# rpusb.net
KiCad netlist of a schematic drawn in EAGLE
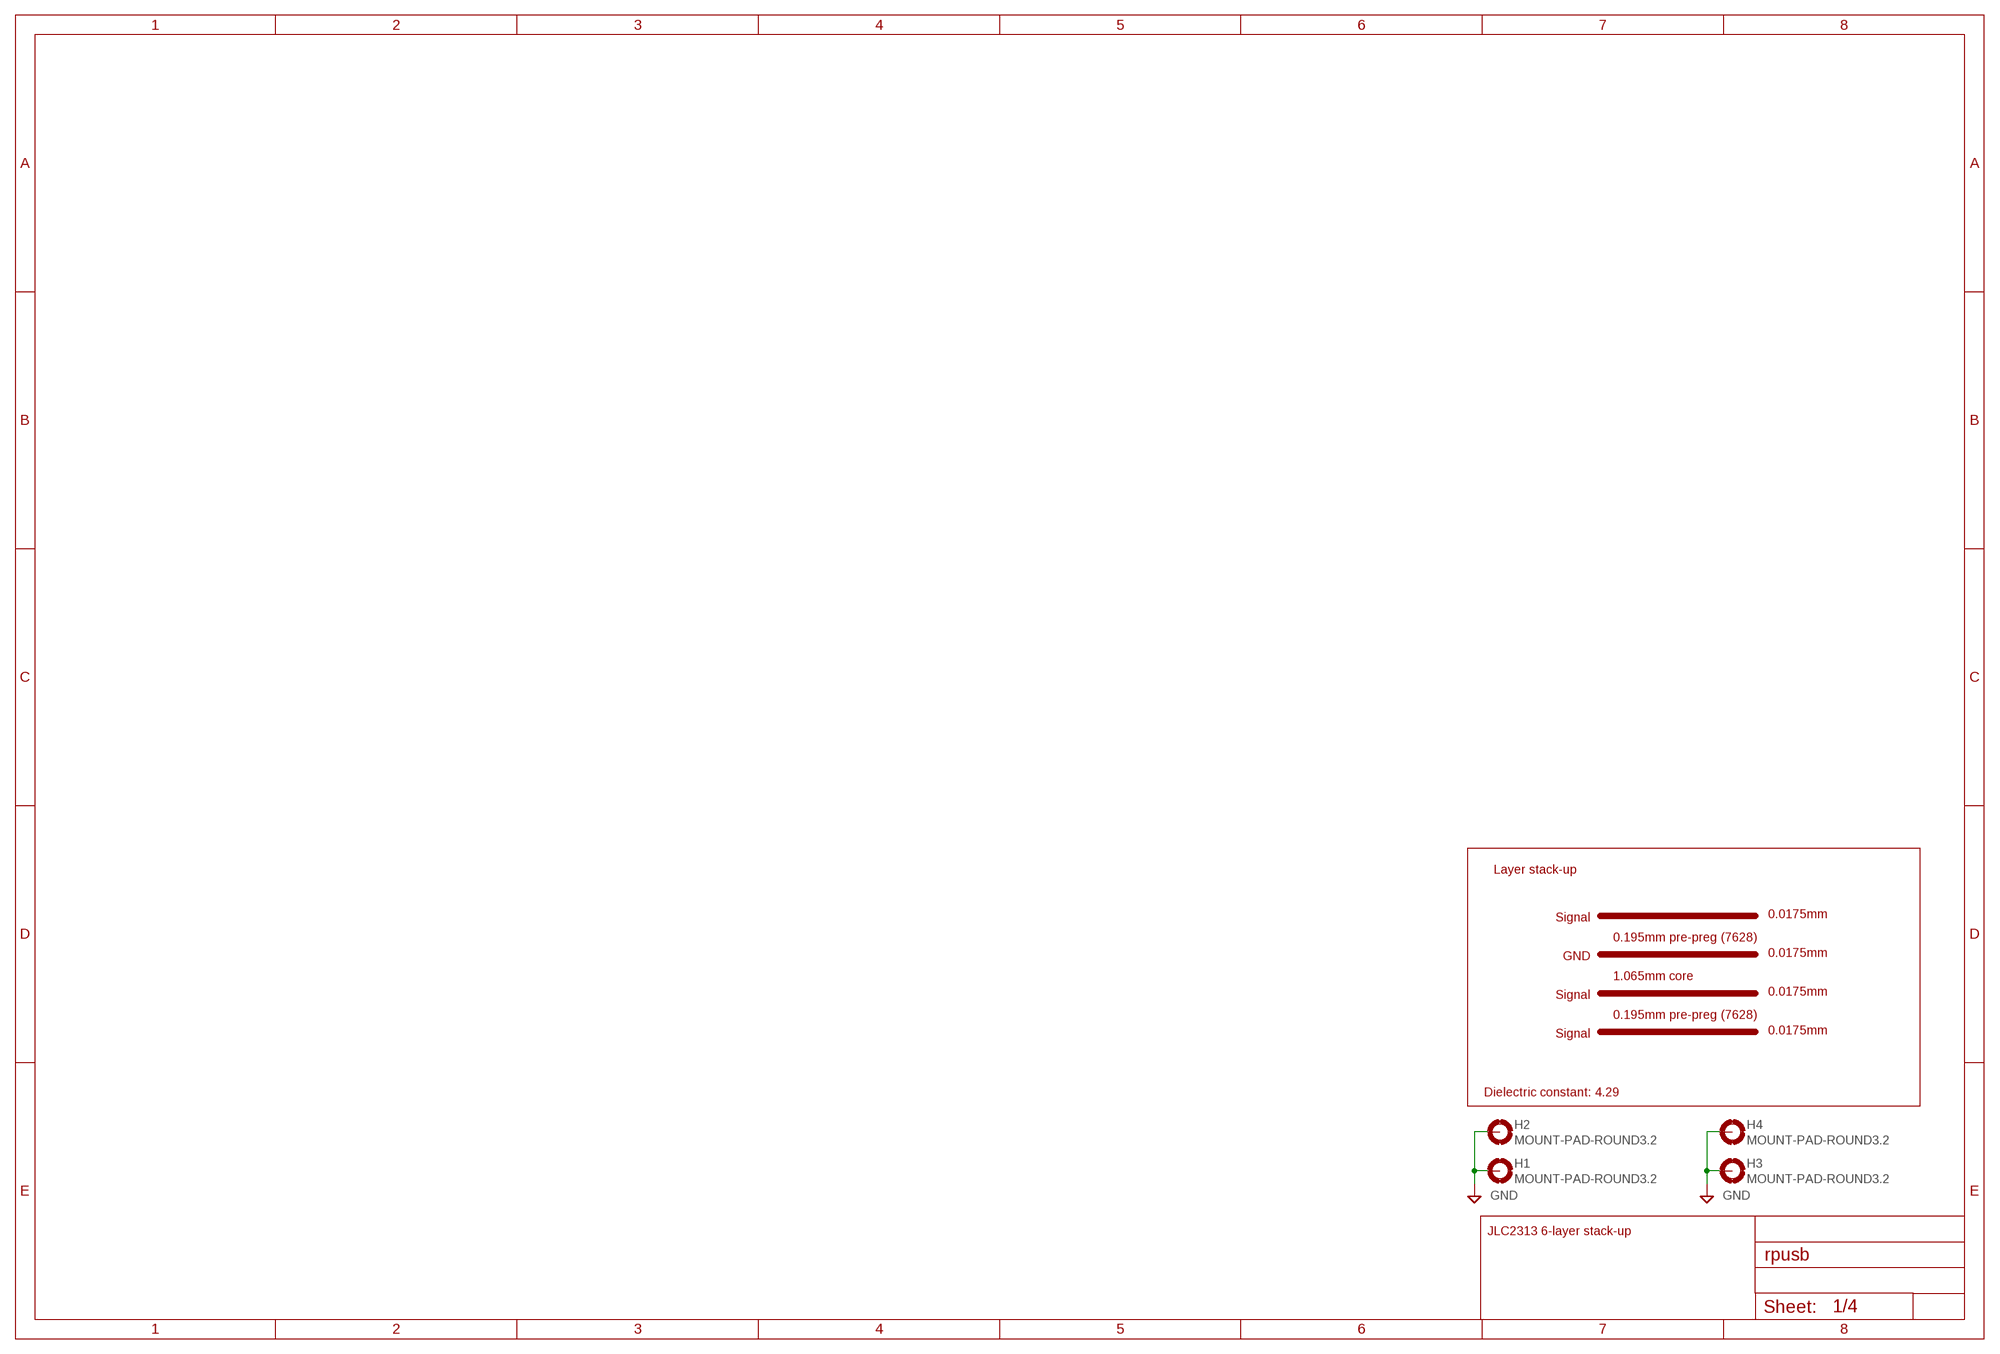
[diagram p0: schematic, sheet 1]
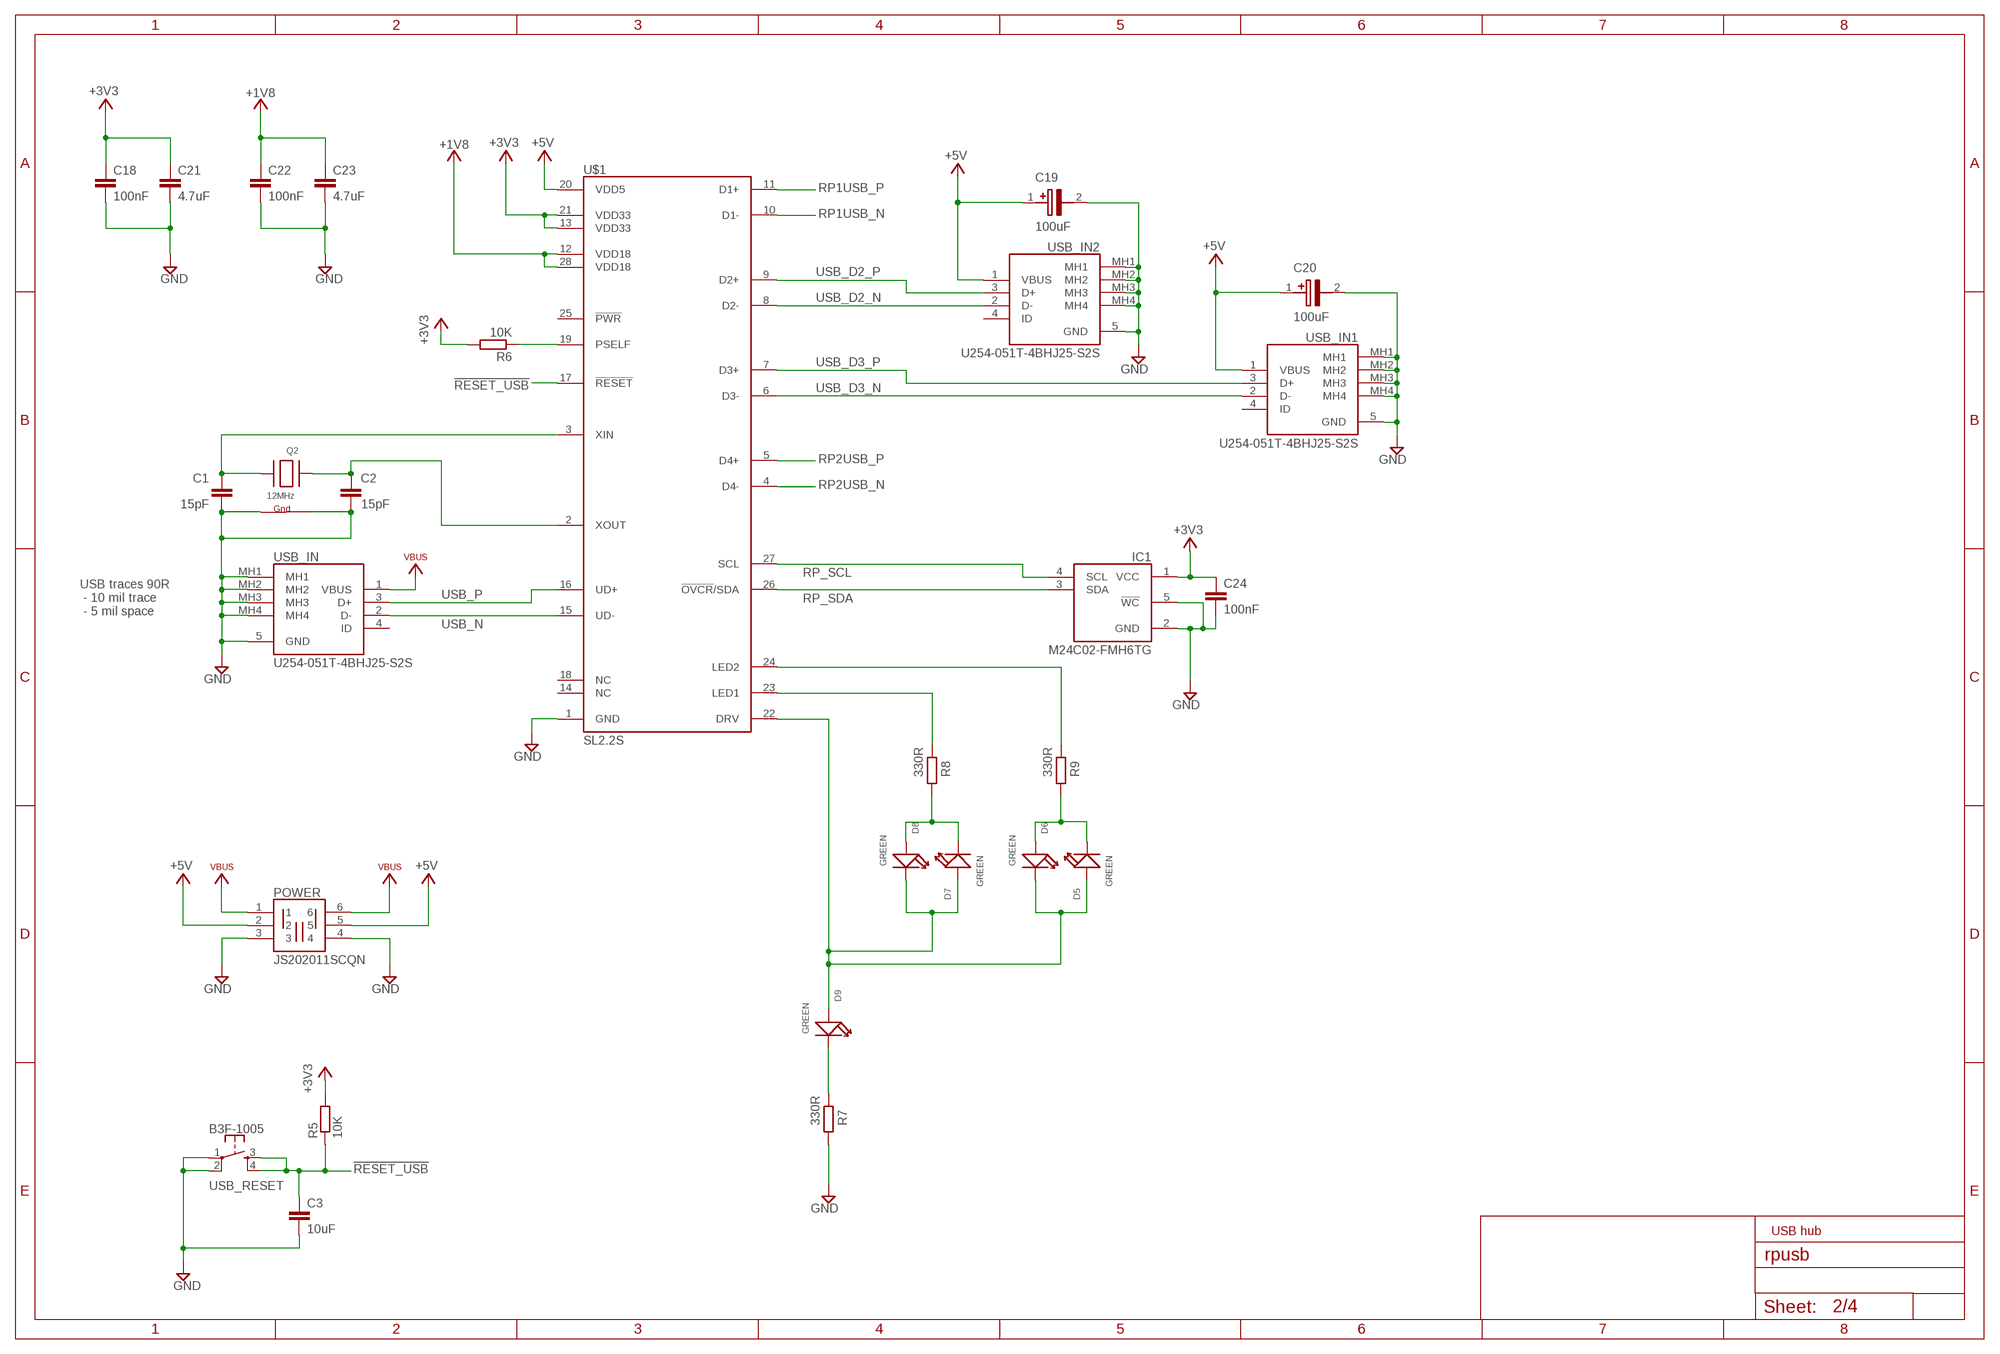
[diagram p1: schematic, sheet 2]
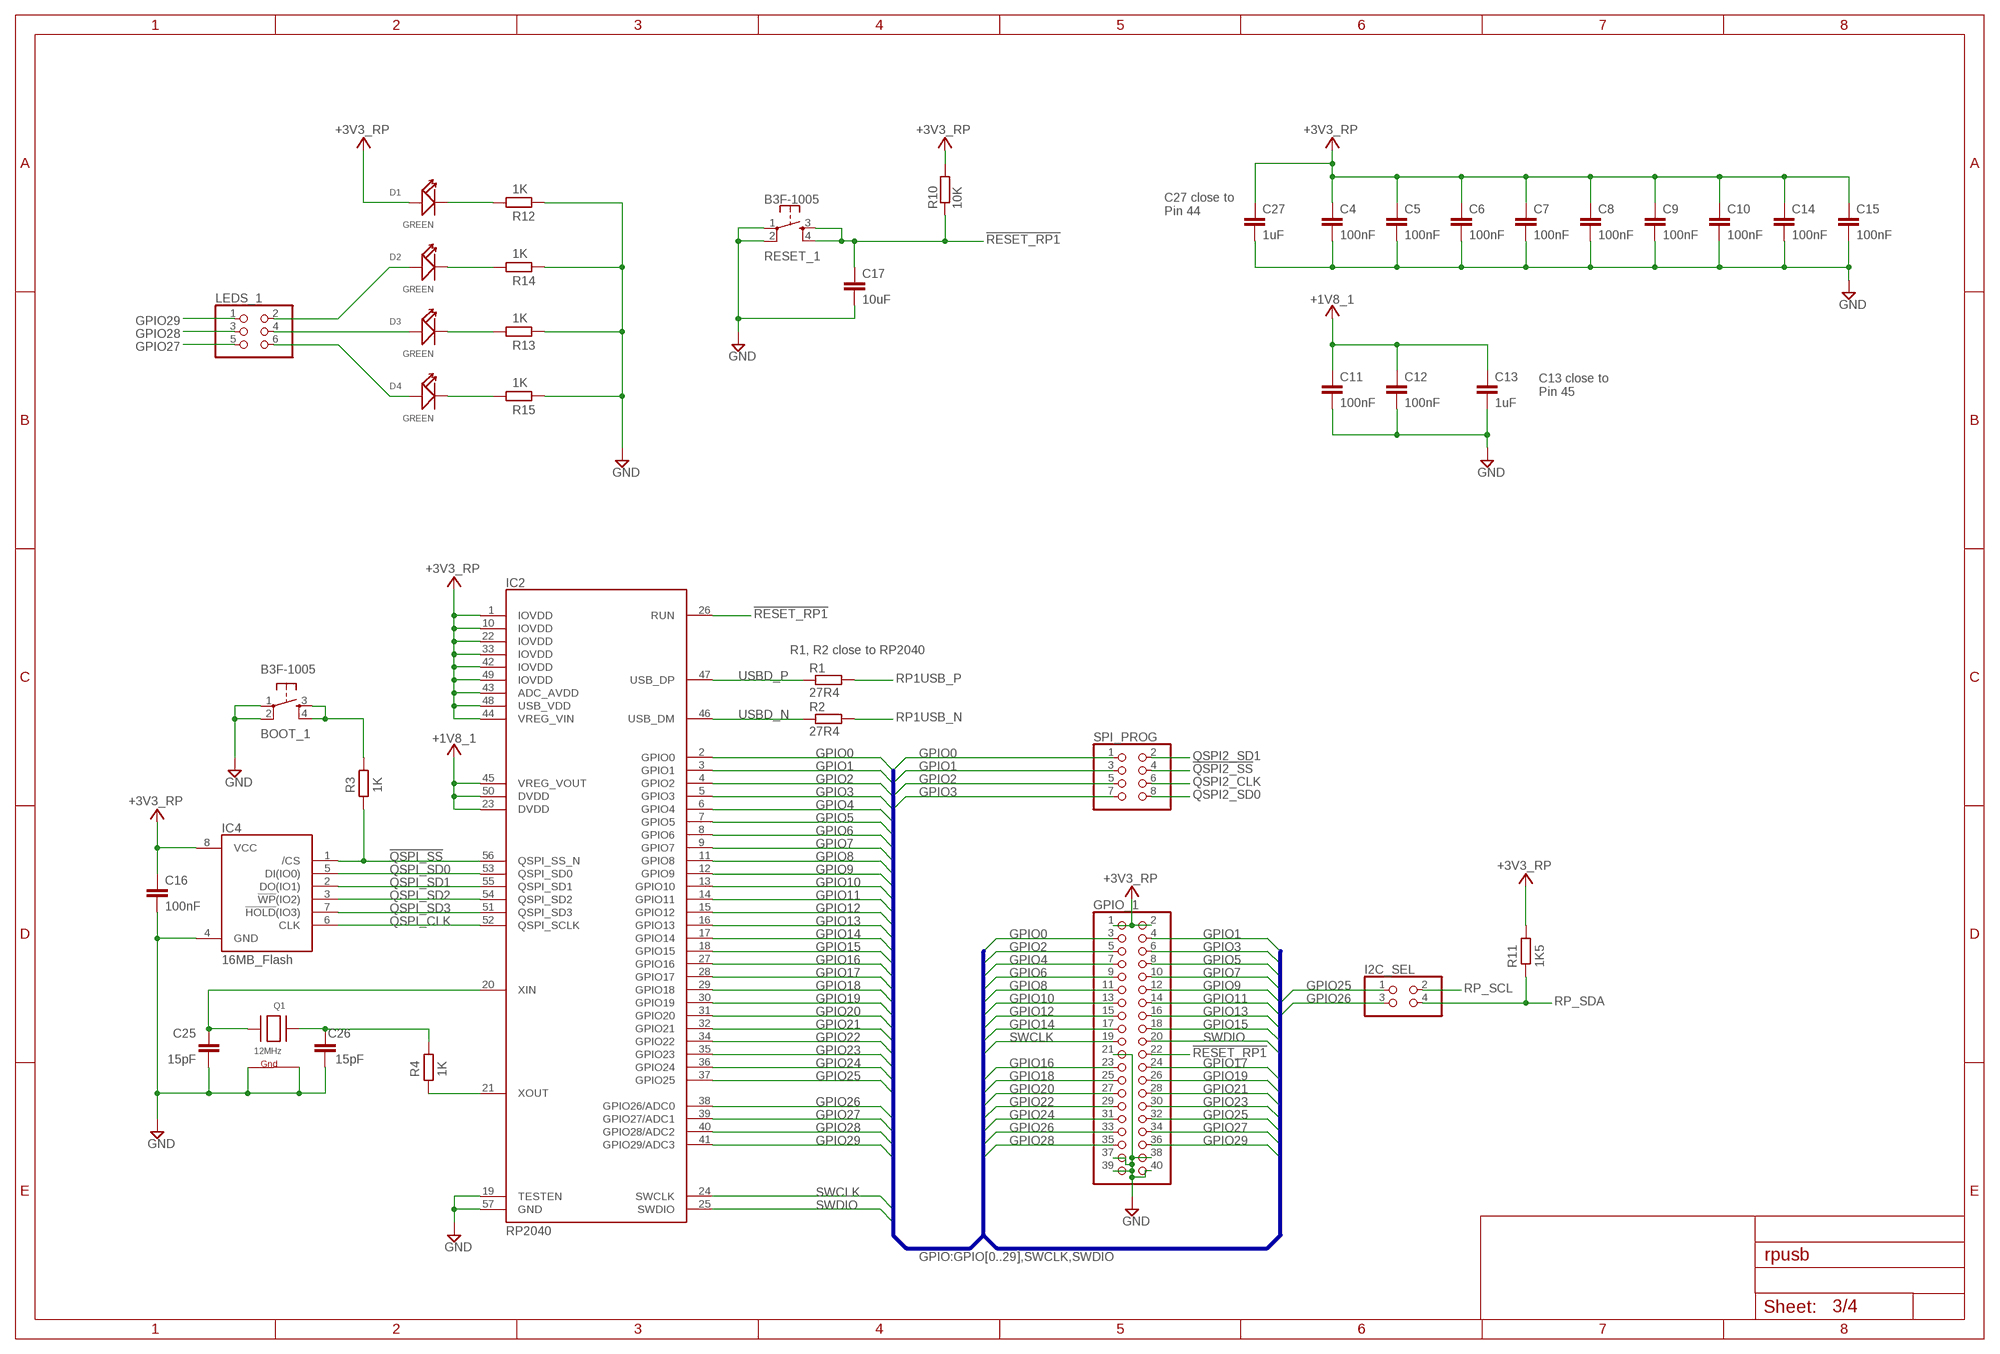
[diagram p2: schematic, sheet 3]
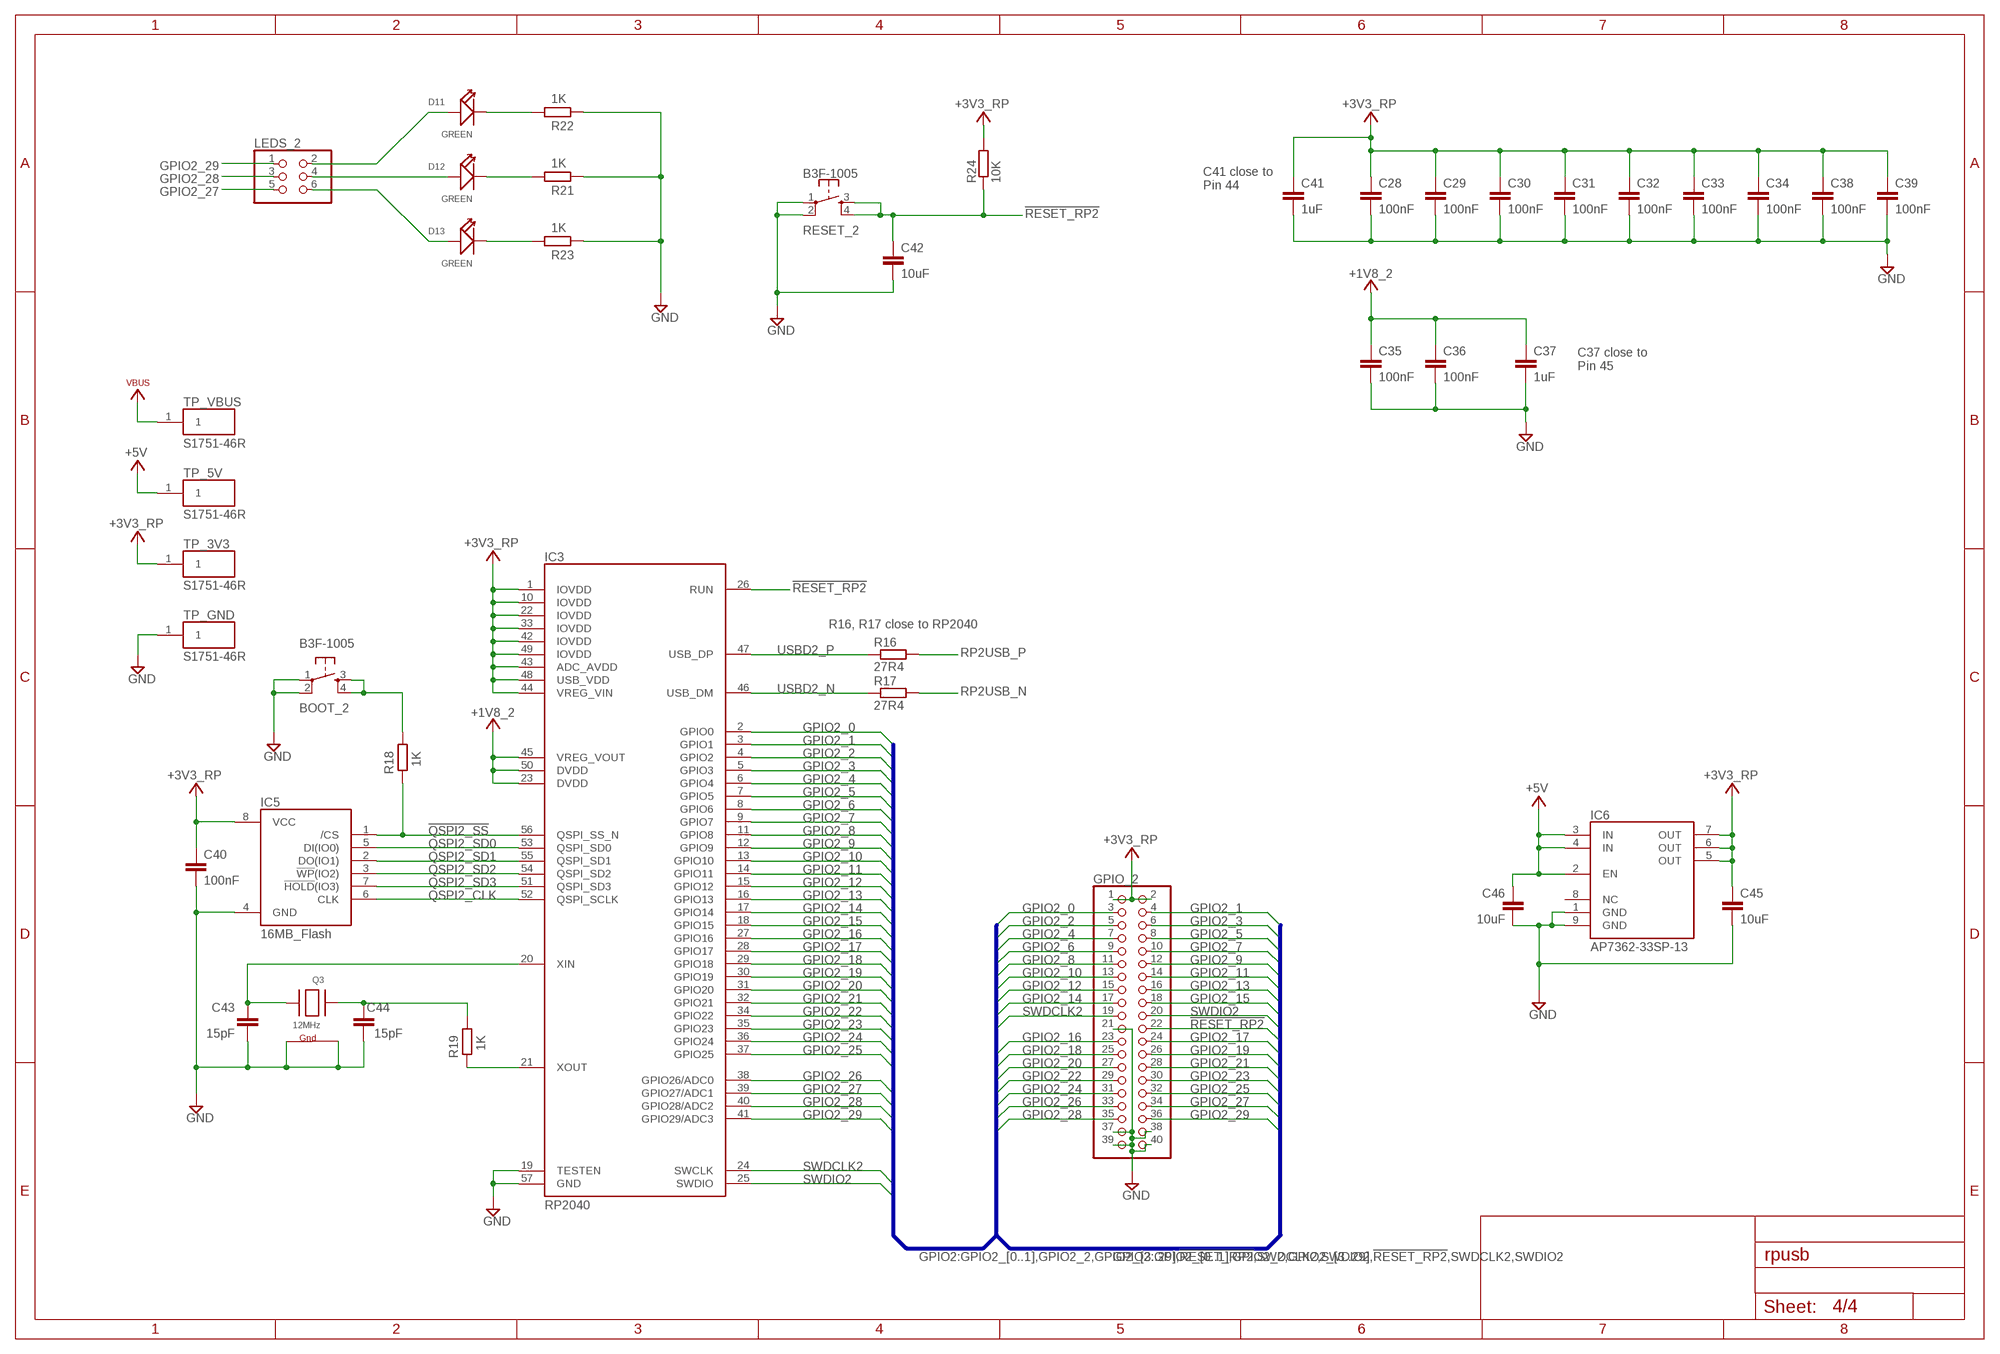
[diagram p3: schematic, sheet 4]

(export (version "E")
  (design (tool "Eeschema 10.0.6"))
  (components
    (comp (ref "C1")
      (value "15pF")
      (footprint "eagle-import:C0201")
      (libsource (lib "eagle-import") (part "C-EUC0201"))
    )
    (comp (ref "C2")
      (value "15pF")
      (footprint "eagle-import:C0201")
      (libsource (lib "eagle-import") (part "C-EUC0201"))
    )
    (comp (ref "C3")
      (value "10uF")
      (footprint "eagle-import:C0402")
      (fields (field (name "USE") "CL05A106MP5NUNC"))
      (libsource (lib "eagle-import") (part "C-EUC0402"))
    )
    (comp (ref "C18")
      (value "100nF")
      (footprint "eagle-import:C0201")
      (libsource (lib "eagle-import") (part "C-EUC0201"))
    )
    (comp (ref "C19")
      (value "100uF")
      (footprint "eagle-import:CAPAE530X550N")
      (fields
        (field (name "MANUFACTURER_PART_NUMBER") "865080142007")
        (field (name "MOUSER_PART_NUMBER") "710-865080142007")
      )
      (libsource (lib "eagle-import") (part "865080142007"))
    )
    (comp (ref "C20")
      (value "100uF")
      (footprint "eagle-import:CAPAE530X550N")
      (fields
        (field (name "MANUFACTURER_PART_NUMBER") "865080142007")
        (field (name "MOUSER_PART_NUMBER") "710-865080142007")
      )
      (libsource (lib "eagle-import") (part "865080142007"))
    )
    (comp (ref "C21")
      (value "4.7uF")
      (footprint "eagle-import:C0402")
      (libsource (lib "eagle-import") (part "C-EUC0402"))
    )
    (comp (ref "C22")
      (value "100nF")
      (footprint "eagle-import:C0201")
      (libsource (lib "eagle-import") (part "C-EUC0201"))
    )
    (comp (ref "C23")
      (value "4.7uF")
      (footprint "eagle-import:C0402")
      (libsource (lib "eagle-import") (part "C-EUC0402"))
    )
    (comp (ref "C24")
      (value "100nF")
      (footprint "eagle-import:C0201")
      (libsource (lib "eagle-import") (part "C-EUC0201"))
    )
    (comp (ref "D5")
      (value "GREEN")
      (footprint "eagle-import:LED-0603")
      (fields (field (name "MPN") "19-217-BHC-ZL1M2RY-3T"))
      (libsource (lib "eagle-import") (part "SMD-LED-CLEAR-BLUE(0603)"))
    )
    (comp (ref "D6")
      (value "GREEN")
      (footprint "eagle-import:LED-0603")
      (fields (field (name "MPN") "19-217-BHC-ZL1M2RY-3T"))
      (libsource (lib "eagle-import") (part "SMD-LED-CLEAR-BLUE(0603)"))
    )
    (comp (ref "D7")
      (value "GREEN")
      (footprint "eagle-import:LED-0603")
      (fields (field (name "MPN") "19-217-BHC-ZL1M2RY-3T"))
      (libsource (lib "eagle-import") (part "SMD-LED-CLEAR-BLUE(0603)"))
    )
    (comp (ref "D8")
      (value "GREEN")
      (footprint "eagle-import:LED-0603")
      (fields (field (name "MPN") "19-217-BHC-ZL1M2RY-3T"))
      (libsource (lib "eagle-import") (part "SMD-LED-CLEAR-BLUE(0603)"))
    )
    (comp (ref "D9")
      (value "GREEN")
      (footprint "eagle-import:LED-0603")
      (fields (field (name "MPN") "19-217-BHC-ZL1M2RY-3T"))
      (libsource (lib "eagle-import") (part "SMD-LED-CLEAR-BLUE(0603)"))
    )
    (comp (ref "IC1")
      (value "M24C02-FMH6TG")
      (footprint "eagle-import:M24C32FMH6TG")
      (fields (field (name "MOUSER_PART_NUMBER") "511-M24C02-FMH6TG"))
      (libsource (lib "eagle-import") (part "M24C02-FMH6TG"))
    )
    (comp (ref "POWER")
      (value "JS202011SCQN")
      (footprint "eagle-import:JS202011SCQN")
      (fields (field (name "MOUSER_PART_NUMBER") "611-JS202011SCQN"))
      (libsource (lib "eagle-import") (part "JS202011SCQN"))
    )
    (comp (ref "Q2")
      (value "12MHz")
      (footprint "eagle-import:NX3225")
      (libsource (lib "eagle-import") (part "XTAL-4-3225"))
    )
    (comp (ref "R5")
      (value "10K")
      (footprint "eagle-import:R0201")
      (fields (field (name "USE") "CR0201-JW-103GLF"))
      (libsource (lib "eagle-import") (part "R-EU_R0201"))
    )
    (comp (ref "R6")
      (value "10K")
      (footprint "eagle-import:R0201")
      (fields (field (name "USE") "CR0201-JW-103GLF"))
      (libsource (lib "eagle-import") (part "R-EU_R0201"))
    )
    (comp (ref "R7")
      (value "330R")
      (footprint "eagle-import:R0201")
      (libsource (lib "eagle-import") (part "R-EU_R0201"))
    )
    (comp (ref "R8")
      (value "330R")
      (footprint "eagle-import:R0201")
      (libsource (lib "eagle-import") (part "R-EU_R0201"))
    )
    (comp (ref "R9")
      (value "330R")
      (footprint "eagle-import:R0201")
      (libsource (lib "eagle-import") (part "R-EU_R0201"))
    )
    (comp (ref "U$1")
      (value "SL2.2S")
      (footprint "eagle-import:SSOP28-0.635")
      (libsource (lib "eagle-import") (part "SL2.2S"))
    )
    (comp (ref "USB_IN")
      (value "U254-051T-4BHJ25-S2S")
      (footprint "eagle-import:U254051T4BHJ25S2S")
      (libsource (lib "eagle-import") (part "U254-051T-4BHJ25-S2S"))
    )
    (comp (ref "USB_IN1")
      (value "U254-051T-4BHJ25-S2S")
      (footprint "eagle-import:U254051T4BHJ25S2S")
      (libsource (lib "eagle-import") (part "U254-051T-4BHJ25-S2S"))
    )
    (comp (ref "USB_IN2")
      (value "U254-051T-4BHJ25-S2S")
      (footprint "eagle-import:U254051T4BHJ25S2S")
      (libsource (lib "eagle-import") (part "U254-051T-4BHJ25-S2S"))
    )
    (comp (ref "USB_RESET")
      (value "B3F-1005")
      (footprint "eagle-import:TACTILE-PTH")
      (fields (field (name "USE") "B3F-1005"))
      (libsource (lib "eagle-import") (part "TAC_SWITCHPTH"))
    )
    (comp (ref "BOOT_1")
      (value "B3F-1005")
      (footprint "eagle-import:TACTILE-PTH")
      (fields (field (name "USE") "B3F-1005"))
      (libsource (lib "eagle-import") (part "TAC_SWITCHPTH"))
    )
    (comp (ref "C4")
      (value "100nF")
      (footprint "eagle-import:C0201")
      (libsource (lib "eagle-import") (part "C-EUC0201"))
    )
    (comp (ref "C5")
      (value "100nF")
      (footprint "eagle-import:C0201")
      (libsource (lib "eagle-import") (part "C-EUC0201"))
    )
    (comp (ref "C6")
      (value "100nF")
      (footprint "eagle-import:C0201")
      (libsource (lib "eagle-import") (part "C-EUC0201"))
    )
    (comp (ref "C7")
      (value "100nF")
      (footprint "eagle-import:C0201")
      (libsource (lib "eagle-import") (part "C-EUC0201"))
    )
    (comp (ref "C8")
      (value "100nF")
      (footprint "eagle-import:C0201")
      (libsource (lib "eagle-import") (part "C-EUC0201"))
    )
    (comp (ref "C9")
      (value "100nF")
      (footprint "eagle-import:C0201")
      (libsource (lib "eagle-import") (part "C-EUC0201"))
    )
    (comp (ref "C10")
      (value "100nF")
      (footprint "eagle-import:C0201")
      (libsource (lib "eagle-import") (part "C-EUC0201"))
    )
    (comp (ref "C11")
      (value "100nF")
      (footprint "eagle-import:C0201")
      (libsource (lib "eagle-import") (part "C-EUC0201"))
    )
    (comp (ref "C12")
      (value "100nF")
      (footprint "eagle-import:C0201")
      (libsource (lib "eagle-import") (part "C-EUC0201"))
    )
    (comp (ref "C13")
      (value "1uF")
      (footprint "eagle-import:C0201")
      (libsource (lib "eagle-import") (part "C-EUC0201"))
    )
    (comp (ref "C14")
      (value "100nF")
      (footprint "eagle-import:C0201")
      (libsource (lib "eagle-import") (part "C-EUC0201"))
    )
    (comp (ref "C15")
      (value "100nF")
      (footprint "eagle-import:C0201")
      (libsource (lib "eagle-import") (part "C-EUC0201"))
    )
    (comp (ref "C16")
      (value "100nF")
      (footprint "eagle-import:C0201")
      (libsource (lib "eagle-import") (part "C-EUC0201"))
    )
    (comp (ref "C17")
      (value "10uF")
      (footprint "eagle-import:C0402")
      (fields (field (name "USE") "CL05A106MP5NUNC"))
      (libsource (lib "eagle-import") (part "C-EUC0402"))
    )
    (comp (ref "C25")
      (value "15pF")
      (footprint "eagle-import:C0201")
      (libsource (lib "eagle-import") (part "C-EUC0201"))
    )
    (comp (ref "C26")
      (value "15pF")
      (footprint "eagle-import:C0201")
      (libsource (lib "eagle-import") (part "C-EUC0201"))
    )
    (comp (ref "C27")
      (value "1uF")
      (footprint "eagle-import:C0201")
      (libsource (lib "eagle-import") (part "C-EUC0201"))
    )
    (comp (ref "D1")
      (value "GREEN")
      (footprint "eagle-import:LED-0603")
      (fields (field (name "MPN") "19-217-BHC-ZL1M2RY-3T"))
      (libsource (lib "eagle-import") (part "SMD-LED-CLEAR-BLUE(0603)"))
    )
    (comp (ref "D2")
      (value "GREEN")
      (footprint "eagle-import:LED-0603")
      (fields (field (name "MPN") "19-217-BHC-ZL1M2RY-3T"))
      (libsource (lib "eagle-import") (part "SMD-LED-CLEAR-BLUE(0603)"))
    )
    (comp (ref "D3")
      (value "GREEN")
      (footprint "eagle-import:LED-0603")
      (fields (field (name "MPN") "19-217-BHC-ZL1M2RY-3T"))
      (libsource (lib "eagle-import") (part "SMD-LED-CLEAR-BLUE(0603)"))
    )
    (comp (ref "D4")
      (value "GREEN")
      (footprint "eagle-import:LED-0603")
      (fields (field (name "MPN") "19-217-BHC-ZL1M2RY-3T"))
      (libsource (lib "eagle-import") (part "SMD-LED-CLEAR-BLUE(0603)"))
    )
    (comp (ref "GPIO_1")
      (value "PINHD-2X20")
      (footprint "eagle-import:2X20")
      (libsource (lib "eagle-import") (part "PINHD-2X20"))
    )
    (comp (ref "I2C_SEL")
      (value "PINHD-2X2")
      (footprint "eagle-import:2X02")
      (libsource (lib "eagle-import") (part "PINHD-2X2"))
    )
    (comp (ref "IC2")
      (value "RP2040")
      (footprint "eagle-import:QFN40P700X700X90-57N")
      (libsource (lib "eagle-import") (part "RP2040"))
    )
    (comp (ref "IC4")
      (value "16MB_Flash")
      (footprint "eagle-import:SOIC127P790X216-8N")
      (fields
        (field (name "ARROW_PART_NUMBER") "W25Q128JVSIM TR")
        (field (name "MOUSER_PART_NUMBER") "454-W25Q128JVSIMTR")
      )
      (libsource (lib "eagle-import") (part "W25Q128JVSIM_TR"))
    )
    (comp (ref "LEDS_1")
      (value "PINHD-2X3")
      (footprint "eagle-import:2X03")
      (libsource (lib "eagle-import") (part "PINHD-2X3"))
    )
    (comp (ref "Q1")
      (value "12MHz")
      (footprint "eagle-import:NX3225")
      (libsource (lib "eagle-import") (part "XTAL-4-3225"))
    )
    (comp (ref "R1")
      (value "27R4")
      (footprint "eagle-import:R0201")
      (libsource (lib "eagle-import") (part "R-EU_R0201"))
    )
    (comp (ref "R2")
      (value "27R4")
      (footprint "eagle-import:R0201")
      (libsource (lib "eagle-import") (part "R-EU_R0201"))
    )
    (comp (ref "R3")
      (value "1K")
      (footprint "eagle-import:R0201")
      (libsource (lib "eagle-import") (part "R-EU_R0201"))
    )
    (comp (ref "R4")
      (value "1K")
      (footprint "eagle-import:R0201")
      (libsource (lib "eagle-import") (part "R-EU_R0201"))
    )
    (comp (ref "R10")
      (value "10K")
      (footprint "eagle-import:R0201")
      (fields (field (name "USE") "CR0201-JW-103GLF"))
      (libsource (lib "eagle-import") (part "R-EU_R0201"))
    )
    (comp (ref "R11")
      (value "1K5")
      (footprint "eagle-import:R0201")
      (libsource (lib "eagle-import") (part "R-EU_R0201"))
    )
    (comp (ref "R12")
      (value "1K")
      (footprint "eagle-import:R0201")
      (libsource (lib "eagle-import") (part "R-EU_R0201"))
    )
    (comp (ref "R13")
      (value "1K")
      (footprint "eagle-import:R0201")
      (libsource (lib "eagle-import") (part "R-EU_R0201"))
    )
    (comp (ref "R14")
      (value "1K")
      (footprint "eagle-import:R0201")
      (libsource (lib "eagle-import") (part "R-EU_R0201"))
    )
    (comp (ref "R15")
      (value "1K")
      (footprint "eagle-import:R0201")
      (libsource (lib "eagle-import") (part "R-EU_R0201"))
    )
    (comp (ref "RESET_1")
      (value "B3F-1005")
      (footprint "eagle-import:TACTILE-PTH")
      (fields (field (name "USE") "B3F-1005"))
      (libsource (lib "eagle-import") (part "TAC_SWITCHPTH"))
    )
    (comp (ref "SPI_PROG")
      (value "PINHD-2X4")
      (footprint "eagle-import:2X04")
      (libsource (lib "eagle-import") (part "PINHD-2X4"))
    )
    (comp (ref "H1")
      (value "MOUNT-PAD-ROUND3.2")
      (footprint "eagle-import:3,2-PAD")
      (libsource (lib "eagle-import") (part "MOUNT-PAD-ROUND3.2"))
    )
    (comp (ref "H2")
      (value "MOUNT-PAD-ROUND3.2")
      (footprint "eagle-import:3,2-PAD")
      (libsource (lib "eagle-import") (part "MOUNT-PAD-ROUND3.2"))
    )
    (comp (ref "H3")
      (value "MOUNT-PAD-ROUND3.2")
      (footprint "eagle-import:3,2-PAD")
      (libsource (lib "eagle-import") (part "MOUNT-PAD-ROUND3.2"))
    )
    (comp (ref "H4")
      (value "MOUNT-PAD-ROUND3.2")
      (footprint "eagle-import:3,2-PAD")
      (libsource (lib "eagle-import") (part "MOUNT-PAD-ROUND3.2"))
    )
    (comp (ref "BOOT_2")
      (value "B3F-1005")
      (footprint "eagle-import:TACTILE-PTH")
      (fields (field (name "USE") "B3F-1005"))
      (libsource (lib "eagle-import") (part "TAC_SWITCHPTH"))
    )
    (comp (ref "C28")
      (value "100nF")
      (footprint "eagle-import:C0201")
      (libsource (lib "eagle-import") (part "C-EUC0201"))
    )
    (comp (ref "C29")
      (value "100nF")
      (footprint "eagle-import:C0201")
      (libsource (lib "eagle-import") (part "C-EUC0201"))
    )
    (comp (ref "C30")
      (value "100nF")
      (footprint "eagle-import:C0201")
      (libsource (lib "eagle-import") (part "C-EUC0201"))
    )
    (comp (ref "C31")
      (value "100nF")
      (footprint "eagle-import:C0201")
      (libsource (lib "eagle-import") (part "C-EUC0201"))
    )
    (comp (ref "C32")
      (value "100nF")
      (footprint "eagle-import:C0201")
      (libsource (lib "eagle-import") (part "C-EUC0201"))
    )
    (comp (ref "C33")
      (value "100nF")
      (footprint "eagle-import:C0201")
      (libsource (lib "eagle-import") (part "C-EUC0201"))
    )
    (comp (ref "C34")
      (value "100nF")
      (footprint "eagle-import:C0201")
      (libsource (lib "eagle-import") (part "C-EUC0201"))
    )
    (comp (ref "C35")
      (value "100nF")
      (footprint "eagle-import:C0201")
      (libsource (lib "eagle-import") (part "C-EUC0201"))
    )
    (comp (ref "C36")
      (value "100nF")
      (footprint "eagle-import:C0201")
      (libsource (lib "eagle-import") (part "C-EUC0201"))
    )
    (comp (ref "C37")
      (value "1uF")
      (footprint "eagle-import:C0201")
      (libsource (lib "eagle-import") (part "C-EUC0201"))
    )
    (comp (ref "C38")
      (value "100nF")
      (footprint "eagle-import:C0201")
      (libsource (lib "eagle-import") (part "C-EUC0201"))
    )
    (comp (ref "C39")
      (value "100nF")
      (footprint "eagle-import:C0201")
      (libsource (lib "eagle-import") (part "C-EUC0201"))
    )
    (comp (ref "C40")
      (value "100nF")
      (footprint "eagle-import:C0201")
      (libsource (lib "eagle-import") (part "C-EUC0201"))
    )
    (comp (ref "C41")
      (value "1uF")
      (footprint "eagle-import:C0201")
      (libsource (lib "eagle-import") (part "C-EUC0201"))
    )
    (comp (ref "C42")
      (value "10uF")
      (footprint "eagle-import:C0402")
      (fields (field (name "USE") "CL05A106MP5NUNC"))
      (libsource (lib "eagle-import") (part "C-EUC0402"))
    )
    (comp (ref "C43")
      (value "15pF")
      (footprint "eagle-import:C0201")
      (libsource (lib "eagle-import") (part "C-EUC0201"))
    )
    (comp (ref "C44")
      (value "15pF")
      (footprint "eagle-import:C0201")
      (libsource (lib "eagle-import") (part "C-EUC0201"))
    )
    (comp (ref "C45")
      (value "10uF")
      (footprint "eagle-import:C0402")
      (fields (field (name "USE") "CL05A106MP5NUNC"))
      (libsource (lib "eagle-import") (part "C-EUC0402"))
    )
    (comp (ref "C46")
      (value "10uF")
      (footprint "eagle-import:C0402")
      (fields (field (name "USE") "CL05A106MP5NUNC"))
      (libsource (lib "eagle-import") (part "C-EUC0402"))
    )
    (comp (ref "D11")
      (value "GREEN")
      (footprint "eagle-import:LED-0603")
      (fields (field (name "MPN") "19-217-BHC-ZL1M2RY-3T"))
      (libsource (lib "eagle-import") (part "SMD-LED-CLEAR-BLUE(0603)"))
    )
    (comp (ref "D12")
      (value "GREEN")
      (footprint "eagle-import:LED-0603")
      (fields (field (name "MPN") "19-217-BHC-ZL1M2RY-3T"))
      (libsource (lib "eagle-import") (part "SMD-LED-CLEAR-BLUE(0603)"))
    )
    (comp (ref "D13")
      (value "GREEN")
      (footprint "eagle-import:LED-0603")
      (fields (field (name "MPN") "19-217-BHC-ZL1M2RY-3T"))
      (libsource (lib "eagle-import") (part "SMD-LED-CLEAR-BLUE(0603)"))
    )
    (comp (ref "GPIO_2")
      (value "PINHD-2X20")
      (footprint "eagle-import:2X20")
      (libsource (lib "eagle-import") (part "PINHD-2X20"))
    )
    (comp (ref "IC3")
      (value "RP2040")
      (footprint "eagle-import:QFN40P700X700X90-57N")
      (libsource (lib "eagle-import") (part "RP2040"))
    )
    (comp (ref "IC5")
      (value "16MB_Flash")
      (footprint "eagle-import:SOIC127P790X216-8N")
      (fields
        (field (name "ARROW_PART_NUMBER") "W25Q128JVSIM TR")
        (field (name "MOUSER_PART_NUMBER") "454-W25Q128JVSIMTR")
      )
      (libsource (lib "eagle-import") (part "W25Q128JVSIM_TR"))
    )
    (comp (ref "IC6")
      (value "AP7362-33SP-13")
      (footprint "eagle-import:SOIC127P600X163-9N")
      (fields (field (name "MOUSER_PART_NUMBER") "621-AP7362-33SP-13"))
      (libsource (lib "eagle-import") (part "AP7362-33SP-13"))
    )
    (comp (ref "LEDS_2")
      (value "PINHD-2X3")
      (footprint "eagle-import:2X03")
      (libsource (lib "eagle-import") (part "PINHD-2X3"))
    )
    (comp (ref "Q3")
      (value "12MHz")
      (footprint "eagle-import:NX3225")
      (libsource (lib "eagle-import") (part "XTAL-4-3225"))
    )
    (comp (ref "R16")
      (value "27R4")
      (footprint "eagle-import:R0201")
      (libsource (lib "eagle-import") (part "R-EU_R0201"))
    )
    (comp (ref "R17")
      (value "27R4")
      (footprint "eagle-import:R0201")
      (libsource (lib "eagle-import") (part "R-EU_R0201"))
    )
    (comp (ref "R18")
      (value "1K")
      (footprint "eagle-import:R0201")
      (libsource (lib "eagle-import") (part "R-EU_R0201"))
    )
    (comp (ref "R19")
      (value "1K")
      (footprint "eagle-import:R0201")
      (libsource (lib "eagle-import") (part "R-EU_R0201"))
    )
    (comp (ref "R21")
      (value "1K")
      (footprint "eagle-import:R0201")
      (libsource (lib "eagle-import") (part "R-EU_R0201"))
    )
    (comp (ref "R22")
      (value "1K")
      (footprint "eagle-import:R0201")
      (libsource (lib "eagle-import") (part "R-EU_R0201"))
    )
    (comp (ref "R23")
      (value "1K")
      (footprint "eagle-import:R0201")
      (libsource (lib "eagle-import") (part "R-EU_R0201"))
    )
    (comp (ref "R24")
      (value "10K")
      (footprint "eagle-import:R0201")
      (fields (field (name "USE") "CR0201-JW-103GLF"))
      (libsource (lib "eagle-import") (part "R-EU_R0201"))
    )
    (comp (ref "RESET_2")
      (value "B3F-1005")
      (footprint "eagle-import:TACTILE-PTH")
      (fields (field (name "USE") "B3F-1005"))
      (libsource (lib "eagle-import") (part "TAC_SWITCHPTH"))
    )
    (comp (ref "TP_3V3")
      (value "S1751-46R")
      (footprint "eagle-import:S175146R")
      (fields (field (name "MOUSER_PART_NUMBER") "855-S1751-46R"))
      (libsource (lib "eagle-import") (part "S1751-46R"))
    )
    (comp (ref "TP_5V")
      (value "S1751-46R")
      (footprint "eagle-import:S175146R")
      (fields (field (name "MOUSER_PART_NUMBER") "855-S1751-46R"))
      (libsource (lib "eagle-import") (part "S1751-46R"))
    )
    (comp (ref "TP_GND")
      (value "S1751-46R")
      (footprint "eagle-import:S175146R")
      (fields (field (name "MOUSER_PART_NUMBER") "855-S1751-46R"))
      (libsource (lib "eagle-import") (part "S1751-46R"))
    )
    (comp (ref "TP_VBUS")
      (value "S1751-46R")
      (footprint "eagle-import:S175146R")
      (fields (field (name "MOUSER_PART_NUMBER") "855-S1751-46R"))
      (libsource (lib "eagle-import") (part "S1751-46R"))
    )
  )
  (nets
    (net (code "1") (name "+1V8") (class "Default")
      (node (ref "C22") (pin "1") (pinfunction "1_1") (pintype "passive"))
      (node (ref "C23") (pin "1") (pinfunction "1_1") (pintype "passive"))
      (node (ref "U$1") (pin "12") (pinfunction "VDD18_12") (pintype "bidirectional"))
      (node (ref "U$1") (pin "28") (pinfunction "VDD18_28") (pintype "bidirectional"))
    )
    (net (code "2") (name "+1V8_1") (class "Default")
      (node (ref "C11") (pin "1") (pinfunction "1_1") (pintype "passive"))
      (node (ref "C12") (pin "1") (pinfunction "1_1") (pintype "passive"))
      (node (ref "C13") (pin "1") (pinfunction "1_1") (pintype "passive"))
      (node (ref "IC2") (pin "23") (pinfunction "DVDD_23") (pintype "bidirectional"))
      (node (ref "IC2") (pin "45") (pinfunction "VREG_VOUT_45") (pintype "bidirectional"))
      (node (ref "IC2") (pin "50") (pinfunction "DVDD_50") (pintype "bidirectional"))
    )
    (net (code "3") (name "+1V8_2") (class "Default")
      (node (ref "C35") (pin "1") (pinfunction "1_1") (pintype "passive"))
      (node (ref "C36") (pin "1") (pinfunction "1_1") (pintype "passive"))
      (node (ref "C37") (pin "1") (pinfunction "1_1") (pintype "passive"))
      (node (ref "IC3") (pin "23") (pinfunction "DVDD_23") (pintype "bidirectional"))
      (node (ref "IC3") (pin "45") (pinfunction "VREG_VOUT_45") (pintype "bidirectional"))
      (node (ref "IC3") (pin "50") (pinfunction "DVDD_50") (pintype "bidirectional"))
    )
    (net (code "4") (name "+3V3") (class "Default")
      (node (ref "C18") (pin "1") (pinfunction "1_1") (pintype "passive"))
      (node (ref "C21") (pin "1") (pinfunction "1_1") (pintype "passive"))
      (node (ref "C24") (pin "1") (pinfunction "1_1") (pintype "passive"))
      (node (ref "IC1") (pin "1") (pinfunction "VCC_1") (pintype "bidirectional"))
      (node (ref "R5") (pin "2") (pinfunction "2_2") (pintype "passive"))
      (node (ref "R6") (pin "2") (pinfunction "2_2") (pintype "passive"))
      (node (ref "U$1") (pin "13") (pinfunction "VDD33_13") (pintype "bidirectional"))
      (node (ref "U$1") (pin "21") (pinfunction "VDD33_21") (pintype "bidirectional"))
    )
    (net (code "5") (name "+3V3_RP") (class "Default")
      (node (ref "C10") (pin "1") (pinfunction "1_1") (pintype "passive"))
      (node (ref "C14") (pin "1") (pinfunction "1_1") (pintype "passive"))
      (node (ref "C15") (pin "1") (pinfunction "1_1") (pintype "passive"))
      (node (ref "C16") (pin "1") (pinfunction "1_1") (pintype "passive"))
      (node (ref "C27") (pin "1") (pinfunction "1_1") (pintype "passive"))
      (node (ref "C28") (pin "1") (pinfunction "1_1") (pintype "passive"))
      (node (ref "C29") (pin "1") (pinfunction "1_1") (pintype "passive"))
      (node (ref "C30") (pin "1") (pinfunction "1_1") (pintype "passive"))
      (node (ref "C31") (pin "1") (pinfunction "1_1") (pintype "passive"))
      (node (ref "C32") (pin "1") (pinfunction "1_1") (pintype "passive"))
      (node (ref "C33") (pin "1") (pinfunction "1_1") (pintype "passive"))
      (node (ref "C34") (pin "1") (pinfunction "1_1") (pintype "passive"))
      (node (ref "C38") (pin "1") (pinfunction "1_1") (pintype "passive"))
      (node (ref "C39") (pin "1") (pinfunction "1_1") (pintype "passive"))
      (node (ref "C4") (pin "1") (pinfunction "1_1") (pintype "passive"))
      (node (ref "C40") (pin "1") (pinfunction "1_1") (pintype "passive"))
      (node (ref "C41") (pin "1") (pinfunction "1_1") (pintype "passive"))
      (node (ref "C45") (pin "1") (pinfunction "1_1") (pintype "passive"))
      (node (ref "C5") (pin "1") (pinfunction "1_1") (pintype "passive"))
      (node (ref "C6") (pin "1") (pinfunction "1_1") (pintype "passive"))
      (node (ref "C7") (pin "1") (pinfunction "1_1") (pintype "passive"))
      (node (ref "C8") (pin "1") (pinfunction "1_1") (pintype "passive"))
      (node (ref "C9") (pin "1") (pinfunction "1_1") (pintype "passive"))
      (node (ref "D1") (pin "+") (pinfunction "+_+") (pintype "passive"))
      (node (ref "GPIO_1") (pin "1") (pinfunction "1_1") (pintype "passive"))
      (node (ref "GPIO_1") (pin "2") (pinfunction "2_2") (pintype "passive"))
      (node (ref "GPIO_2") (pin "1") (pinfunction "1_1") (pintype "passive"))
      (node (ref "GPIO_2") (pin "2") (pinfunction "2_2") (pintype "passive"))
      (node (ref "IC2") (pin "1") (pinfunction "IOVDD_1") (pintype "bidirectional"))
      (node (ref "IC2") (pin "10") (pinfunction "IOVDD_10") (pintype "bidirectional"))
      (node (ref "IC2") (pin "22") (pinfunction "IOVDD_22") (pintype "bidirectional"))
      (node (ref "IC2") (pin "33") (pinfunction "IOVDD_33") (pintype "bidirectional"))
      (node (ref "IC2") (pin "42") (pinfunction "IOVDD_42") (pintype "bidirectional"))
      (node (ref "IC2") (pin "43") (pinfunction "ADC_AVDD_43") (pintype "bidirectional"))
      (node (ref "IC2") (pin "44") (pinfunction "VREG_VIN_44") (pintype "bidirectional"))
      (node (ref "IC2") (pin "48") (pinfunction "USB_VDD_48") (pintype "bidirectional"))
      (node (ref "IC2") (pin "49") (pinfunction "IOVDD_49") (pintype "bidirectional"))
      (node (ref "IC3") (pin "1") (pinfunction "IOVDD_1") (pintype "bidirectional"))
      (node (ref "IC3") (pin "10") (pinfunction "IOVDD_10") (pintype "bidirectional"))
      (node (ref "IC3") (pin "22") (pinfunction "IOVDD_22") (pintype "bidirectional"))
      (node (ref "IC3") (pin "33") (pinfunction "IOVDD_33") (pintype "bidirectional"))
      (node (ref "IC3") (pin "42") (pinfunction "IOVDD_42") (pintype "bidirectional"))
      (node (ref "IC3") (pin "43") (pinfunction "ADC_AVDD_43") (pintype "bidirectional"))
      (node (ref "IC3") (pin "44") (pinfunction "VREG_VIN_44") (pintype "bidirectional"))
      (node (ref "IC3") (pin "48") (pinfunction "USB_VDD_48") (pintype "bidirectional"))
      (node (ref "IC3") (pin "49") (pinfunction "IOVDD_49") (pintype "bidirectional"))
      (node (ref "IC4") (pin "8") (pinfunction "VCC_8") (pintype "bidirectional"))
      (node (ref "IC5") (pin "8") (pinfunction "VCC_8") (pintype "bidirectional"))
      (node (ref "IC6") (pin "5") (pinfunction "OUT_5") (pintype "bidirectional"))
      (node (ref "IC6") (pin "6") (pinfunction "OUT_6") (pintype "bidirectional"))
      (node (ref "IC6") (pin "7") (pinfunction "OUT_7") (pintype "bidirectional"))
      (node (ref "R10") (pin "2") (pinfunction "2_2") (pintype "passive"))
      (node (ref "R11") (pin "1") (pinfunction "1_1") (pintype "passive"))
      (node (ref "R24") (pin "2") (pinfunction "2_2") (pintype "passive"))
      (node (ref "TP_3V3") (pin "1") (pinfunction "1_1") (pintype "bidirectional"))
    )
    (net (code "6") (name "+5V") (class "Default")
      (node (ref "C19") (pin "1") (pinfunction "+_1") (pintype "bidirectional"))
      (node (ref "C20") (pin "1") (pinfunction "+_1") (pintype "bidirectional"))
      (node (ref "C46") (pin "1") (pinfunction "1_1") (pintype "passive"))
      (node (ref "IC6") (pin "2") (pinfunction "EN_2") (pintype "bidirectional"))
      (node (ref "IC6") (pin "3") (pinfunction "IN_3") (pintype "bidirectional"))
      (node (ref "IC6") (pin "4") (pinfunction "IN_4") (pintype "bidirectional"))
      (node (ref "POWER") (pin "2") (pinfunction "2_2") (pintype "bidirectional"))
      (node (ref "POWER") (pin "5") (pinfunction "5_5") (pintype "bidirectional"))
      (node (ref "TP_5V") (pin "1") (pinfunction "1_1") (pintype "bidirectional"))
      (node (ref "U$1") (pin "20") (pinfunction "VDD5_20") (pintype "bidirectional"))
      (node (ref "USB_IN1") (pin "1") (pinfunction "VBUS_1") (pintype "bidirectional"))
      (node (ref "USB_IN2") (pin "1") (pinfunction "VBUS_1") (pintype "bidirectional"))
    )
    (net (code "9") (name "GND") (class "Default")
      (node (ref "BOOT_1") (pin "1") (pinfunction "1_1") (pintype "passive"))
      (node (ref "BOOT_1") (pin "2") (pinfunction "2_2") (pintype "passive"))
      (node (ref "BOOT_2") (pin "1") (pinfunction "1_1") (pintype "passive"))
      (node (ref "BOOT_2") (pin "2") (pinfunction "2_2") (pintype "passive"))
      (node (ref "C1") (pin "2") (pinfunction "2_2") (pintype "passive"))
      (node (ref "C10") (pin "2") (pinfunction "2_2") (pintype "passive"))
      (node (ref "C11") (pin "2") (pinfunction "2_2") (pintype "passive"))
      (node (ref "C12") (pin "2") (pinfunction "2_2") (pintype "passive"))
      (node (ref "C13") (pin "2") (pinfunction "2_2") (pintype "passive"))
      (node (ref "C14") (pin "2") (pinfunction "2_2") (pintype "passive"))
      (node (ref "C15") (pin "2") (pinfunction "2_2") (pintype "passive"))
      (node (ref "C16") (pin "2") (pinfunction "2_2") (pintype "passive"))
      (node (ref "C17") (pin "2") (pinfunction "2_2") (pintype "passive"))
      (node (ref "C18") (pin "2") (pinfunction "2_2") (pintype "passive"))
      (node (ref "C19") (pin "2") (pinfunction "-_2") (pintype "bidirectional"))
      (node (ref "C2") (pin "2") (pinfunction "2_2") (pintype "passive"))
      (node (ref "C20") (pin "2") (pinfunction "-_2") (pintype "bidirectional"))
      (node (ref "C21") (pin "2") (pinfunction "2_2") (pintype "passive"))
      (node (ref "C22") (pin "2") (pinfunction "2_2") (pintype "passive"))
      (node (ref "C23") (pin "2") (pinfunction "2_2") (pintype "passive"))
      (node (ref "C24") (pin "2") (pinfunction "2_2") (pintype "passive"))
      (node (ref "C25") (pin "2") (pinfunction "2_2") (pintype "passive"))
      (node (ref "C26") (pin "2") (pinfunction "2_2") (pintype "passive"))
      (node (ref "C27") (pin "2") (pinfunction "2_2") (pintype "passive"))
      (node (ref "C28") (pin "2") (pinfunction "2_2") (pintype "passive"))
      (node (ref "C29") (pin "2") (pinfunction "2_2") (pintype "passive"))
      (node (ref "C3") (pin "2") (pinfunction "2_2") (pintype "passive"))
      (node (ref "C30") (pin "2") (pinfunction "2_2") (pintype "passive"))
      (node (ref "C31") (pin "2") (pinfunction "2_2") (pintype "passive"))
      (node (ref "C32") (pin "2") (pinfunction "2_2") (pintype "passive"))
      (node (ref "C33") (pin "2") (pinfunction "2_2") (pintype "passive"))
      (node (ref "C34") (pin "2") (pinfunction "2_2") (pintype "passive"))
      (node (ref "C35") (pin "2") (pinfunction "2_2") (pintype "passive"))
      (node (ref "C36") (pin "2") (pinfunction "2_2") (pintype "passive"))
      (node (ref "C37") (pin "2") (pinfunction "2_2") (pintype "passive"))
      (node (ref "C38") (pin "2") (pinfunction "2_2") (pintype "passive"))
      (node (ref "C39") (pin "2") (pinfunction "2_2") (pintype "passive"))
      (node (ref "C4") (pin "2") (pinfunction "2_2") (pintype "passive"))
      (node (ref "C40") (pin "2") (pinfunction "2_2") (pintype "passive"))
      (node (ref "C41") (pin "2") (pinfunction "2_2") (pintype "passive"))
      (node (ref "C42") (pin "2") (pinfunction "2_2") (pintype "passive"))
      (node (ref "C43") (pin "2") (pinfunction "2_2") (pintype "passive"))
      (node (ref "C44") (pin "2") (pinfunction "2_2") (pintype "passive"))
      (node (ref "C45") (pin "2") (pinfunction "2_2") (pintype "passive"))
      (node (ref "C46") (pin "2") (pinfunction "2_2") (pintype "passive"))
      (node (ref "C5") (pin "2") (pinfunction "2_2") (pintype "passive"))
      (node (ref "C6") (pin "2") (pinfunction "2_2") (pintype "passive"))
      (node (ref "C7") (pin "2") (pinfunction "2_2") (pintype "passive"))
      (node (ref "C8") (pin "2") (pinfunction "2_2") (pintype "passive"))
      (node (ref "C9") (pin "2") (pinfunction "2_2") (pintype "passive"))
      (node (ref "GPIO_1") (pin "21") (pinfunction "21_21") (pintype "passive"))
      (node (ref "GPIO_1") (pin "37") (pinfunction "37_37") (pintype "passive"))
      (node (ref "GPIO_1") (pin "38") (pinfunction "38_38") (pintype "passive"))
      (node (ref "GPIO_1") (pin "39") (pinfunction "39_39") (pintype "passive"))
      (node (ref "GPIO_1") (pin "40") (pinfunction "40_40") (pintype "passive"))
      (node (ref "GPIO_2") (pin "21") (pinfunction "21_21") (pintype "passive"))
      (node (ref "GPIO_2") (pin "37") (pinfunction "37_37") (pintype "passive"))
      (node (ref "GPIO_2") (pin "38") (pinfunction "38_38") (pintype "passive"))
      (node (ref "GPIO_2") (pin "39") (pinfunction "39_39") (pintype "passive"))
      (node (ref "GPIO_2") (pin "40") (pinfunction "40_40") (pintype "passive"))
      (node (ref "H1") (pin "B3,2") (pinfunction "MOUNT_B3,2") (pintype "passive"))
      (node (ref "H2") (pin "B3,2") (pinfunction "MOUNT_B3,2") (pintype "passive"))
      (node (ref "H3") (pin "B3,2") (pinfunction "MOUNT_B3,2") (pintype "passive"))
      (node (ref "H4") (pin "B3,2") (pinfunction "MOUNT_B3,2") (pintype "passive"))
      (node (ref "IC1") (pin "2") (pinfunction "GND_2") (pintype "bidirectional"))
      (node (ref "IC1") (pin "5") (pinfunction "~{WC}_5") (pintype "bidirectional"))
      (node (ref "IC2") (pin "19") (pinfunction "TESTEN_19") (pintype "bidirectional"))
      (node (ref "IC2") (pin "57") (pinfunction "GND_57") (pintype "bidirectional"))
      (node (ref "IC3") (pin "19") (pinfunction "TESTEN_19") (pintype "bidirectional"))
      (node (ref "IC3") (pin "57") (pinfunction "GND_57") (pintype "bidirectional"))
      (node (ref "IC4") (pin "4") (pinfunction "GND_4") (pintype "bidirectional"))
      (node (ref "IC5") (pin "4") (pinfunction "GND_4") (pintype "bidirectional"))
      (node (ref "IC6") (pin "1") (pinfunction "GND_1") (pintype "bidirectional"))
      (node (ref "IC6") (pin "9") (pinfunction "GND_9") (pintype "bidirectional"))
      (node (ref "POWER") (pin "3") (pinfunction "3_3") (pintype "bidirectional"))
      (node (ref "POWER") (pin "4") (pinfunction "4_4") (pintype "bidirectional"))
      (node (ref "Q1") (pin "2") (pinfunction "G2_2") (pintype "power_in"))
      (node (ref "Q1") (pin "4") (pinfunction "G1_4") (pintype "power_in"))
      (node (ref "Q2") (pin "2") (pinfunction "G2_2") (pintype "power_in"))
      (node (ref "Q2") (pin "4") (pinfunction "G1_4") (pintype "power_in"))
      (node (ref "Q3") (pin "2") (pinfunction "G2_2") (pintype "power_in"))
      (node (ref "Q3") (pin "4") (pinfunction "G1_4") (pintype "power_in"))
      (node (ref "R12") (pin "2") (pinfunction "2_2") (pintype "passive"))
      (node (ref "R13") (pin "2") (pinfunction "2_2") (pintype "passive"))
      (node (ref "R14") (pin "2") (pinfunction "2_2") (pintype "passive"))
      (node (ref "R15") (pin "2") (pinfunction "2_2") (pintype "passive"))
      (node (ref "R21") (pin "2") (pinfunction "2_2") (pintype "passive"))
      (node (ref "R22") (pin "2") (pinfunction "2_2") (pintype "passive"))
      (node (ref "R23") (pin "2") (pinfunction "2_2") (pintype "passive"))
      (node (ref "R7") (pin "1") (pinfunction "1_1") (pintype "passive"))
      (node (ref "RESET_1") (pin "1") (pinfunction "1_1") (pintype "passive"))
      (node (ref "RESET_1") (pin "2") (pinfunction "2_2") (pintype "passive"))
      (node (ref "RESET_2") (pin "1") (pinfunction "1_1") (pintype "passive"))
      (node (ref "RESET_2") (pin "2") (pinfunction "2_2") (pintype "passive"))
      (node (ref "TP_GND") (pin "1") (pinfunction "1_1") (pintype "bidirectional"))
      (node (ref "U$1") (pin "1") (pinfunction "GND_1") (pintype "bidirectional"))
      (node (ref "USB_IN") (pin "5") (pinfunction "GND_5") (pintype "bidirectional"))
      (node (ref "USB_IN") (pin "MH1") (pinfunction "MH1_MH1") (pintype "bidirectional"))
      (node (ref "USB_IN") (pin "MH2") (pinfunction "MH2_MH2") (pintype "bidirectional"))
      (node (ref "USB_IN") (pin "MH3") (pinfunction "MH3_MH3") (pintype "bidirectional"))
      (node (ref "USB_IN") (pin "MH4") (pinfunction "MH4_MH4") (pintype "bidirectional"))
      (node (ref "USB_IN1") (pin "5") (pinfunction "GND_5") (pintype "bidirectional"))
      (node (ref "USB_IN1") (pin "MH1") (pinfunction "MH1_MH1") (pintype "bidirectional"))
      (node (ref "USB_IN1") (pin "MH2") (pinfunction "MH2_MH2") (pintype "bidirectional"))
      (node (ref "USB_IN1") (pin "MH3") (pinfunction "MH3_MH3") (pintype "bidirectional"))
      (node (ref "USB_IN1") (pin "MH4") (pinfunction "MH4_MH4") (pintype "bidirectional"))
      (node (ref "USB_IN2") (pin "5") (pinfunction "GND_5") (pintype "bidirectional"))
      (node (ref "USB_IN2") (pin "MH1") (pinfunction "MH1_MH1") (pintype "bidirectional"))
      (node (ref "USB_IN2") (pin "MH2") (pinfunction "MH2_MH2") (pintype "bidirectional"))
      (node (ref "USB_IN2") (pin "MH3") (pinfunction "MH3_MH3") (pintype "bidirectional"))
      (node (ref "USB_IN2") (pin "MH4") (pinfunction "MH4_MH4") (pintype "bidirectional"))
      (node (ref "USB_RESET") (pin "1") (pinfunction "1_1") (pintype "passive"))
      (node (ref "USB_RESET") (pin "2") (pinfunction "2_2") (pintype "passive"))
    )
    (net (code "10") (name "GPIO0") (class "Default")
      (node (ref "GPIO_1") (pin "3") (pinfunction "3_3") (pintype "passive"))
      (node (ref "IC2") (pin "2") (pinfunction "GPIO0_2") (pintype "bidirectional"))
      (node (ref "SPI_PROG") (pin "1") (pinfunction "1_1") (pintype "passive"))
    )
    (net (code "11") (name "GPIO1") (class "Default")
      (node (ref "GPIO_1") (pin "4") (pinfunction "4_4") (pintype "passive"))
      (node (ref "IC2") (pin "3") (pinfunction "GPIO1_3") (pintype "bidirectional"))
      (node (ref "SPI_PROG") (pin "3") (pinfunction "3_3") (pintype "passive"))
    )
    (net (code "12") (name "GPIO2") (class "Default")
      (node (ref "GPIO_1") (pin "5") (pinfunction "5_5") (pintype "passive"))
      (node (ref "IC2") (pin "4") (pinfunction "GPIO2_4") (pintype "bidirectional"))
      (node (ref "SPI_PROG") (pin "5") (pinfunction "5_5") (pintype "passive"))
    )
    (net (code "13") (name "GPIO2_0") (class "Default")
      (node (ref "GPIO_2") (pin "3") (pinfunction "3_3") (pintype "passive"))
      (node (ref "IC3") (pin "2") (pinfunction "GPIO0_2") (pintype "bidirectional"))
    )
    (net (code "14") (name "GPIO2_1") (class "Default")
      (node (ref "GPIO_2") (pin "4") (pinfunction "4_4") (pintype "passive"))
      (node (ref "IC3") (pin "3") (pinfunction "GPIO1_3") (pintype "bidirectional"))
    )
    (net (code "15") (name "GPIO2_2") (class "Default")
      (node (ref "GPIO_2") (pin "5") (pinfunction "5_5") (pintype "passive"))
      (node (ref "IC3") (pin "4") (pinfunction "GPIO2_4") (pintype "bidirectional"))
    )
    (net (code "16") (name "GPIO2_3") (class "Default")
      (node (ref "GPIO_2") (pin "6") (pinfunction "6_6") (pintype "passive"))
      (node (ref "IC3") (pin "5") (pinfunction "GPIO3_5") (pintype "bidirectional"))
    )
    (net (code "17") (name "GPIO2_4") (class "Default")
      (node (ref "GPIO_2") (pin "7") (pinfunction "7_7") (pintype "passive"))
      (node (ref "IC3") (pin "6") (pinfunction "GPIO4_6") (pintype "bidirectional"))
    )
    (net (code "18") (name "GPIO2_5") (class "Default")
      (node (ref "GPIO_2") (pin "8") (pinfunction "8_8") (pintype "passive"))
      (node (ref "IC3") (pin "7") (pinfunction "GPIO5_7") (pintype "bidirectional"))
    )
    (net (code "19") (name "GPIO2_6") (class "Default")
      (node (ref "GPIO_2") (pin "9") (pinfunction "9_9") (pintype "passive"))
      (node (ref "IC3") (pin "8") (pinfunction "GPIO6_8") (pintype "bidirectional"))
    )
    (net (code "20") (name "GPIO2_7") (class "Default")
      (node (ref "GPIO_2") (pin "10") (pinfunction "10_10") (pintype "passive"))
      (node (ref "IC3") (pin "9") (pinfunction "GPIO7_9") (pintype "bidirectional"))
    )
    (net (code "21") (name "GPIO2_8") (class "Default")
      (node (ref "GPIO_2") (pin "11") (pinfunction "11_11") (pintype "passive"))
      (node (ref "IC3") (pin "11") (pinfunction "GPIO8_11") (pintype "bidirectional"))
    )
    (net (code "22") (name "GPIO2_9") (class "Default")
      (node (ref "GPIO_2") (pin "12") (pinfunction "12_12") (pintype "passive"))
      (node (ref "IC3") (pin "12") (pinfunction "GPIO9_12") (pintype "bidirectional"))
    )
    (net (code "23") (name "GPIO2_10") (class "Default")
      (node (ref "GPIO_2") (pin "13") (pinfunction "13_13") (pintype "passive"))
      (node (ref "IC3") (pin "13") (pinfunction "GPIO10_13") (pintype "bidirectional"))
    )
    (net (code "24") (name "GPIO2_11") (class "Default")
      (node (ref "GPIO_2") (pin "14") (pinfunction "14_14") (pintype "passive"))
      (node (ref "IC3") (pin "14") (pinfunction "GPIO11_14") (pintype "bidirectional"))
    )
    (net (code "25") (name "GPIO2_12") (class "Default")
      (node (ref "GPIO_2") (pin "15") (pinfunction "15_15") (pintype "passive"))
      (node (ref "IC3") (pin "15") (pinfunction "GPIO12_15") (pintype "bidirectional"))
    )
    (net (code "26") (name "GPIO2_13") (class "Default")
      (node (ref "GPIO_2") (pin "16") (pinfunction "16_16") (pintype "passive"))
      (node (ref "IC3") (pin "16") (pinfunction "GPIO13_16") (pintype "bidirectional"))
    )
    (net (code "27") (name "GPIO2_14") (class "Default")
      (node (ref "GPIO_2") (pin "17") (pinfunction "17_17") (pintype "passive"))
      (node (ref "IC3") (pin "17") (pinfunction "GPIO14_17") (pintype "bidirectional"))
    )
    (net (code "28") (name "GPIO2_15") (class "Default")
      (node (ref "GPIO_2") (pin "18") (pinfunction "18_18") (pintype "passive"))
      (node (ref "IC3") (pin "18") (pinfunction "GPIO15_18") (pintype "bidirectional"))
    )
    (net (code "29") (name "GPIO2_16") (class "Default")
      (node (ref "GPIO_2") (pin "23") (pinfunction "23_23") (pintype "passive"))
      (node (ref "IC3") (pin "27") (pinfunction "GPIO16_27") (pintype "bidirectional"))
    )
    (net (code "30") (name "GPIO2_17") (class "Default")
      (node (ref "GPIO_2") (pin "24") (pinfunction "24_24") (pintype "passive"))
      (node (ref "IC3") (pin "28") (pinfunction "GPIO17_28") (pintype "bidirectional"))
    )
    (net (code "31") (name "GPIO2_18") (class "Default")
      (node (ref "GPIO_2") (pin "25") (pinfunction "25_25") (pintype "passive"))
      (node (ref "IC3") (pin "29") (pinfunction "GPIO18_29") (pintype "bidirectional"))
    )
    (net (code "32") (name "GPIO2_19") (class "Default")
      (node (ref "GPIO_2") (pin "26") (pinfunction "26_26") (pintype "passive"))
      (node (ref "IC3") (pin "30") (pinfunction "GPIO19_30") (pintype "bidirectional"))
    )
    (net (code "33") (name "GPIO2_20") (class "Default")
      (node (ref "GPIO_2") (pin "27") (pinfunction "27_27") (pintype "passive"))
      (node (ref "IC3") (pin "31") (pinfunction "GPIO20_31") (pintype "bidirectional"))
    )
    (net (code "34") (name "GPIO2_21") (class "Default")
      (node (ref "GPIO_2") (pin "28") (pinfunction "28_28") (pintype "passive"))
      (node (ref "IC3") (pin "32") (pinfunction "GPIO21_32") (pintype "bidirectional"))
    )
    (net (code "35") (name "GPIO2_22") (class "Default")
      (node (ref "GPIO_2") (pin "29") (pinfunction "29_29") (pintype "passive"))
      (node (ref "IC3") (pin "34") (pinfunction "GPIO22_34") (pintype "bidirectional"))
    )
    (net (code "36") (name "GPIO2_23") (class "Default")
      (node (ref "GPIO_2") (pin "30") (pinfunction "30_30") (pintype "passive"))
      (node (ref "IC3") (pin "35") (pinfunction "GPIO23_35") (pintype "bidirectional"))
    )
    (net (code "37") (name "GPIO2_24") (class "Default")
      (node (ref "GPIO_2") (pin "31") (pinfunction "31_31") (pintype "passive"))
      (node (ref "IC3") (pin "36") (pinfunction "GPIO24_36") (pintype "bidirectional"))
    )
    (net (code "38") (name "GPIO2_25") (class "Default")
      (node (ref "GPIO_2") (pin "32") (pinfunction "32_32") (pintype "passive"))
      (node (ref "IC3") (pin "37") (pinfunction "GPIO25_37") (pintype "bidirectional"))
    )
    (net (code "39") (name "GPIO2_26") (class "Default")
      (node (ref "GPIO_2") (pin "33") (pinfunction "33_33") (pintype "passive"))
      (node (ref "IC3") (pin "38") (pinfunction "GPIO26/ADC0_38") (pintype "bidirectional"))
    )
    (net (code "40") (name "GPIO2_27") (class "Default")
      (node (ref "GPIO_2") (pin "34") (pinfunction "34_34") (pintype "passive"))
      (node (ref "IC3") (pin "39") (pinfunction "GPIO27/ADC1_39") (pintype "bidirectional"))
      (node (ref "LEDS_2") (pin "5") (pinfunction "5_5") (pintype "passive"))
    )
    (net (code "41") (name "GPIO2_28") (class "Default")
      (node (ref "GPIO_2") (pin "35") (pinfunction "35_35") (pintype "passive"))
      (node (ref "IC3") (pin "40") (pinfunction "GPIO28/ADC2_40") (pintype "bidirectional"))
      (node (ref "LEDS_2") (pin "3") (pinfunction "3_3") (pintype "passive"))
    )
    (net (code "42") (name "GPIO2_29") (class "Default")
      (node (ref "GPIO_2") (pin "36") (pinfunction "36_36") (pintype "passive"))
      (node (ref "IC3") (pin "41") (pinfunction "GPIO29/ADC3_41") (pintype "bidirectional"))
      (node (ref "LEDS_2") (pin "1") (pinfunction "1_1") (pintype "passive"))
    )
    (net (code "43") (name "GPIO3") (class "Default")
      (node (ref "GPIO_1") (pin "6") (pinfunction "6_6") (pintype "passive"))
      (node (ref "IC2") (pin "5") (pinfunction "GPIO3_5") (pintype "bidirectional"))
      (node (ref "SPI_PROG") (pin "7") (pinfunction "7_7") (pintype "passive"))
    )
    (net (code "44") (name "GPIO4") (class "Default")
      (node (ref "GPIO_1") (pin "7") (pinfunction "7_7") (pintype "passive"))
      (node (ref "IC2") (pin "6") (pinfunction "GPIO4_6") (pintype "bidirectional"))
    )
    (net (code "45") (name "GPIO5") (class "Default")
      (node (ref "GPIO_1") (pin "8") (pinfunction "8_8") (pintype "passive"))
      (node (ref "IC2") (pin "7") (pinfunction "GPIO5_7") (pintype "bidirectional"))
    )
    (net (code "46") (name "GPIO6") (class "Default")
      (node (ref "GPIO_1") (pin "9") (pinfunction "9_9") (pintype "passive"))
      (node (ref "IC2") (pin "8") (pinfunction "GPIO6_8") (pintype "bidirectional"))
    )
    (net (code "47") (name "GPIO7") (class "Default")
      (node (ref "GPIO_1") (pin "10") (pinfunction "10_10") (pintype "passive"))
      (node (ref "IC2") (pin "9") (pinfunction "GPIO7_9") (pintype "bidirectional"))
    )
    (net (code "48") (name "GPIO8") (class "Default")
      (node (ref "GPIO_1") (pin "11") (pinfunction "11_11") (pintype "passive"))
      (node (ref "IC2") (pin "11") (pinfunction "GPIO8_11") (pintype "bidirectional"))
    )
    (net (code "49") (name "GPIO9") (class "Default")
      (node (ref "GPIO_1") (pin "12") (pinfunction "12_12") (pintype "passive"))
      (node (ref "IC2") (pin "12") (pinfunction "GPIO9_12") (pintype "bidirectional"))
    )
    (net (code "50") (name "GPIO10") (class "Default")
      (node (ref "GPIO_1") (pin "13") (pinfunction "13_13") (pintype "passive"))
      (node (ref "IC2") (pin "13") (pinfunction "GPIO10_13") (pintype "bidirectional"))
    )
    (net (code "51") (name "GPIO11") (class "Default")
      (node (ref "GPIO_1") (pin "14") (pinfunction "14_14") (pintype "passive"))
      (node (ref "IC2") (pin "14") (pinfunction "GPIO11_14") (pintype "bidirectional"))
    )
    (net (code "52") (name "GPIO12") (class "Default")
      (node (ref "GPIO_1") (pin "15") (pinfunction "15_15") (pintype "passive"))
      (node (ref "IC2") (pin "15") (pinfunction "GPIO12_15") (pintype "bidirectional"))
    )
    (net (code "53") (name "GPIO13") (class "Default")
      (node (ref "GPIO_1") (pin "16") (pinfunction "16_16") (pintype "passive"))
      (node (ref "IC2") (pin "16") (pinfunction "GPIO13_16") (pintype "bidirectional"))
    )
    (net (code "54") (name "GPIO14") (class "Default")
      (node (ref "GPIO_1") (pin "17") (pinfunction "17_17") (pintype "passive"))
      (node (ref "IC2") (pin "17") (pinfunction "GPIO14_17") (pintype "bidirectional"))
    )
    (net (code "55") (name "GPIO15") (class "Default")
      (node (ref "GPIO_1") (pin "18") (pinfunction "18_18") (pintype "passive"))
      (node (ref "IC2") (pin "18") (pinfunction "GPIO15_18") (pintype "bidirectional"))
    )
    (net (code "56") (name "GPIO16") (class "Default")
      (node (ref "GPIO_1") (pin "23") (pinfunction "23_23") (pintype "passive"))
      (node (ref "IC2") (pin "27") (pinfunction "GPIO16_27") (pintype "bidirectional"))
    )
    (net (code "57") (name "GPIO17") (class "Default")
      (node (ref "GPIO_1") (pin "24") (pinfunction "24_24") (pintype "passive"))
      (node (ref "IC2") (pin "28") (pinfunction "GPIO17_28") (pintype "bidirectional"))
    )
    (net (code "58") (name "GPIO18") (class "Default")
      (node (ref "GPIO_1") (pin "25") (pinfunction "25_25") (pintype "passive"))
      (node (ref "IC2") (pin "29") (pinfunction "GPIO18_29") (pintype "bidirectional"))
    )
    (net (code "59") (name "GPIO19") (class "Default")
      (node (ref "GPIO_1") (pin "26") (pinfunction "26_26") (pintype "passive"))
      (node (ref "IC2") (pin "30") (pinfunction "GPIO19_30") (pintype "bidirectional"))
    )
    (net (code "60") (name "GPIO20") (class "Default")
      (node (ref "GPIO_1") (pin "27") (pinfunction "27_27") (pintype "passive"))
      (node (ref "IC2") (pin "31") (pinfunction "GPIO20_31") (pintype "bidirectional"))
    )
    (net (code "61") (name "GPIO21") (class "Default")
      (node (ref "GPIO_1") (pin "28") (pinfunction "28_28") (pintype "passive"))
      (node (ref "IC2") (pin "32") (pinfunction "GPIO21_32") (pintype "bidirectional"))
    )
    (net (code "62") (name "GPIO22") (class "Default")
      (node (ref "GPIO_1") (pin "29") (pinfunction "29_29") (pintype "passive"))
      (node (ref "IC2") (pin "34") (pinfunction "GPIO22_34") (pintype "bidirectional"))
    )
    (net (code "63") (name "GPIO23") (class "Default")
      (node (ref "GPIO_1") (pin "30") (pinfunction "30_30") (pintype "passive"))
      (node (ref "IC2") (pin "35") (pinfunction "GPIO23_35") (pintype "bidirectional"))
    )
    (net (code "64") (name "GPIO24") (class "Default")
      (node (ref "GPIO_1") (pin "31") (pinfunction "31_31") (pintype "passive"))
      (node (ref "IC2") (pin "36") (pinfunction "GPIO24_36") (pintype "bidirectional"))
    )
    (net (code "65") (name "GPIO25") (class "Default")
      (node (ref "GPIO_1") (pin "32") (pinfunction "32_32") (pintype "passive"))
      (node (ref "I2C_SEL") (pin "1") (pinfunction "1_1") (pintype "passive"))
      (node (ref "IC2") (pin "37") (pinfunction "GPIO25_37") (pintype "bidirectional"))
    )
    (net (code "66") (name "GPIO26") (class "Default")
      (node (ref "GPIO_1") (pin "33") (pinfunction "33_33") (pintype "passive"))
      (node (ref "I2C_SEL") (pin "3") (pinfunction "3_3") (pintype "passive"))
      (node (ref "IC2") (pin "38") (pinfunction "GPIO26/ADC0_38") (pintype "bidirectional"))
    )
    (net (code "67") (name "GPIO27") (class "Default")
      (node (ref "GPIO_1") (pin "34") (pinfunction "34_34") (pintype "passive"))
      (node (ref "IC2") (pin "39") (pinfunction "GPIO27/ADC1_39") (pintype "bidirectional"))
      (node (ref "LEDS_1") (pin "5") (pinfunction "5_5") (pintype "passive"))
    )
    (net (code "68") (name "GPIO28") (class "Default")
      (node (ref "GPIO_1") (pin "35") (pinfunction "35_35") (pintype "passive"))
      (node (ref "IC2") (pin "40") (pinfunction "GPIO28/ADC2_40") (pintype "bidirectional"))
      (node (ref "LEDS_1") (pin "3") (pinfunction "3_3") (pintype "passive"))
    )
    (net (code "69") (name "GPIO29") (class "Default")
      (node (ref "GPIO_1") (pin "36") (pinfunction "36_36") (pintype "passive"))
      (node (ref "IC2") (pin "41") (pinfunction "GPIO29/ADC3_41") (pintype "bidirectional"))
      (node (ref "LEDS_1") (pin "1") (pinfunction "1_1") (pintype "passive"))
    )
    (net (code "70") (name "Net-(BOOT_1-Pad3)") (class "Default")
      (node (ref "BOOT_1") (pin "3") (pinfunction "3_3") (pintype "passive"))
      (node (ref "BOOT_1") (pin "4") (pinfunction "4_4") (pintype "passive"))
      (node (ref "R3") (pin "1") (pinfunction "1_1") (pintype "passive"))
    )
    (net (code "71") (name "Net-(BOOT_2-Pad3)") (class "Default")
      (node (ref "BOOT_2") (pin "3") (pinfunction "3_3") (pintype "passive"))
      (node (ref "BOOT_2") (pin "4") (pinfunction "4_4") (pintype "passive"))
      (node (ref "R18") (pin "1") (pinfunction "1_1") (pintype "passive"))
    )
    (net (code "72") (name "Net-(D1-Pad-)") (class "Default")
      (node (ref "D1") (pin "-") (pinfunction "-_-") (pintype "passive"))
      (node (ref "R12") (pin "1") (pinfunction "1_1") (pintype "passive"))
    )
    (net (code "73") (name "Net-(D2-Pad+)") (class "Default")
      (node (ref "D2") (pin "+") (pinfunction "+_+") (pintype "passive"))
      (node (ref "LEDS_1") (pin "2") (pinfunction "2_2") (pintype "passive"))
    )
    (net (code "74") (name "Net-(D2-Pad-)") (class "Default")
      (node (ref "D2") (pin "-") (pinfunction "-_-") (pintype "passive"))
      (node (ref "R14") (pin "1") (pinfunction "1_1") (pintype "passive"))
    )
    (net (code "75") (name "Net-(D3-Pad+)") (class "Default")
      (node (ref "D3") (pin "+") (pinfunction "+_+") (pintype "passive"))
      (node (ref "LEDS_1") (pin "4") (pinfunction "4_4") (pintype "passive"))
    )
    (net (code "76") (name "Net-(D3-Pad-)") (class "Default")
      (node (ref "D3") (pin "-") (pinfunction "-_-") (pintype "passive"))
      (node (ref "R13") (pin "1") (pinfunction "1_1") (pintype "passive"))
    )
    (net (code "77") (name "Net-(D4-Pad+)") (class "Default")
      (node (ref "D4") (pin "+") (pinfunction "+_+") (pintype "passive"))
      (node (ref "LEDS_1") (pin "6") (pinfunction "6_6") (pintype "passive"))
    )
    (net (code "78") (name "Net-(D4-Pad-)") (class "Default")
      (node (ref "D4") (pin "-") (pinfunction "-_-") (pintype "passive"))
      (node (ref "R15") (pin "1") (pinfunction "1_1") (pintype "passive"))
    )
    (net (code "79") (name "Net-(D5-Pad-)") (class "Default")
      (node (ref "D5") (pin "-") (pinfunction "-_-") (pintype "passive"))
      (node (ref "D6") (pin "+") (pinfunction "+_+") (pintype "passive"))
      (node (ref "R9") (pin "1") (pinfunction "1_1") (pintype "passive"))
    )
    (net (code "80") (name "Net-(D7-Pad-)") (class "Default")
      (node (ref "D7") (pin "-") (pinfunction "-_-") (pintype "passive"))
      (node (ref "D8") (pin "+") (pinfunction "+_+") (pintype "passive"))
      (node (ref "R8") (pin "1") (pinfunction "1_1") (pintype "passive"))
    )
    (net (code "81") (name "Net-(D9-Pad-)") (class "Default")
      (node (ref "D9") (pin "-") (pinfunction "-_-") (pintype "passive"))
      (node (ref "R7") (pin "2") (pinfunction "2_2") (pintype "passive"))
    )
    (net (code "82") (name "Net-(D11-Pad+)") (class "Default")
      (node (ref "D11") (pin "+") (pinfunction "+_+") (pintype "passive"))
      (node (ref "LEDS_2") (pin "2") (pinfunction "2_2") (pintype "passive"))
    )
    (net (code "83") (name "Net-(D11-Pad-)") (class "Default")
      (node (ref "D11") (pin "-") (pinfunction "-_-") (pintype "passive"))
      (node (ref "R22") (pin "1") (pinfunction "1_1") (pintype "passive"))
    )
    (net (code "84") (name "Net-(D12-Pad+)") (class "Default")
      (node (ref "D12") (pin "+") (pinfunction "+_+") (pintype "passive"))
      (node (ref "LEDS_2") (pin "4") (pinfunction "4_4") (pintype "passive"))
    )
    (net (code "85") (name "Net-(D12-Pad-)") (class "Default")
      (node (ref "D12") (pin "-") (pinfunction "-_-") (pintype "passive"))
      (node (ref "R21") (pin "1") (pinfunction "1_1") (pintype "passive"))
    )
    (net (code "86") (name "Net-(D13-Pad+)") (class "Default")
      (node (ref "D13") (pin "+") (pinfunction "+_+") (pintype "passive"))
      (node (ref "LEDS_2") (pin "6") (pinfunction "6_6") (pintype "passive"))
    )
    (net (code "87") (name "Net-(D13-Pad-)") (class "Default")
      (node (ref "D13") (pin "-") (pinfunction "-_-") (pintype "passive"))
      (node (ref "R23") (pin "1") (pinfunction "1_1") (pintype "passive"))
    )
    (net (code "88") (name "Net-(IC2-XIN)") (class "Default")
      (node (ref "C25") (pin "1") (pinfunction "1_1") (pintype "passive"))
      (node (ref "IC2") (pin "20") (pinfunction "XIN_20") (pintype "bidirectional"))
      (node (ref "Q1") (pin "1") (pinfunction "X1_1") (pintype "bidirectional"))
    )
    (net (code "89") (name "Net-(IC2-XOUT)") (class "Default")
      (node (ref "IC2") (pin "21") (pinfunction "XOUT_21") (pintype "bidirectional"))
      (node (ref "R4") (pin "2") (pinfunction "2_2") (pintype "passive"))
    )
    (net (code "90") (name "Net-(IC3-XIN)") (class "Default")
      (node (ref "C43") (pin "1") (pinfunction "1_1") (pintype "passive"))
      (node (ref "IC3") (pin "20") (pinfunction "XIN_20") (pintype "bidirectional"))
      (node (ref "Q3") (pin "1") (pinfunction "X1_1") (pintype "bidirectional"))
    )
    (net (code "91") (name "Net-(IC3-XOUT)") (class "Default")
      (node (ref "IC3") (pin "21") (pinfunction "XOUT_21") (pintype "bidirectional"))
      (node (ref "R19") (pin "2") (pinfunction "2_2") (pintype "passive"))
    )
    (net (code "92") (name "Net-(Q1-X2)") (class "Default")
      (node (ref "C26") (pin "1") (pinfunction "1_1") (pintype "passive"))
      (node (ref "Q1") (pin "3") (pinfunction "X2_3") (pintype "bidirectional"))
      (node (ref "R4") (pin "1") (pinfunction "1_1") (pintype "passive"))
    )
    (net (code "93") (name "Net-(Q2-X1)") (class "Default")
      (node (ref "C1") (pin "1") (pinfunction "1_1") (pintype "passive"))
      (node (ref "Q2") (pin "1") (pinfunction "X1_1") (pintype "bidirectional"))
      (node (ref "U$1") (pin "3") (pinfunction "XIN_3") (pintype "bidirectional"))
    )
    (net (code "94") (name "Net-(Q2-X2)") (class "Default")
      (node (ref "C2") (pin "1") (pinfunction "1_1") (pintype "passive"))
      (node (ref "Q2") (pin "3") (pinfunction "X2_3") (pintype "bidirectional"))
      (node (ref "U$1") (pin "2") (pinfunction "XOUT_2") (pintype "bidirectional"))
    )
    (net (code "95") (name "Net-(Q3-X2)") (class "Default")
      (node (ref "C44") (pin "1") (pinfunction "1_1") (pintype "passive"))
      (node (ref "Q3") (pin "3") (pinfunction "X2_3") (pintype "bidirectional"))
      (node (ref "R19") (pin "1") (pinfunction "1_1") (pintype "passive"))
    )
    (net (code "96") (name "Net-(U$1-DRV)") (class "Default")
      (node (ref "D5") (pin "+") (pinfunction "+_+") (pintype "passive"))
      (node (ref "D6") (pin "-") (pinfunction "-_-") (pintype "passive"))
      (node (ref "D7") (pin "+") (pinfunction "+_+") (pintype "passive"))
      (node (ref "D8") (pin "-") (pinfunction "-_-") (pintype "passive"))
      (node (ref "D9") (pin "+") (pinfunction "+_+") (pintype "passive"))
      (node (ref "U$1") (pin "22") (pinfunction "DRV_22") (pintype "bidirectional"))
    )
    (net (code "97") (name "Net-(U$1-LED1)") (class "Default")
      (node (ref "R8") (pin "2") (pinfunction "2_2") (pintype "passive"))
      (node (ref "U$1") (pin "23") (pinfunction "LED1_23") (pintype "bidirectional"))
    )
    (net (code "98") (name "Net-(U$1-LED2)") (class "Default")
      (node (ref "R9") (pin "2") (pinfunction "2_2") (pintype "passive"))
      (node (ref "U$1") (pin "24") (pinfunction "LED2_24") (pintype "bidirectional"))
    )
    (net (code "99") (name "Net-(U$1-PSELF)") (class "Default")
      (node (ref "R6") (pin "1") (pinfunction "1_1") (pintype "passive"))
      (node (ref "U$1") (pin "19") (pinfunction "PSELF_19") (pintype "bidirectional"))
    )
    (net (code "100") (name "QSPI2_CLK") (class "Default")
      (node (ref "IC3") (pin "52") (pinfunction "QSPI_SCLK_52") (pintype "bidirectional"))
      (node (ref "IC5") (pin "6") (pinfunction "CLK_6") (pintype "bidirectional"))
      (node (ref "SPI_PROG") (pin "6") (pinfunction "6_6") (pintype "passive"))
    )
    (net (code "101") (name "QSPI2_SD0") (class "Default")
      (node (ref "IC3") (pin "53") (pinfunction "QSPI_SD0_53") (pintype "bidirectional"))
      (node (ref "IC5") (pin "5") (pinfunction "DI(IO0)_5") (pintype "bidirectional"))
      (node (ref "SPI_PROG") (pin "8") (pinfunction "8_8") (pintype "passive"))
    )
    (net (code "102") (name "QSPI2_SD1") (class "Default")
      (node (ref "IC3") (pin "55") (pinfunction "QSPI_SD1_55") (pintype "bidirectional"))
      (node (ref "IC5") (pin "2") (pinfunction "DO(IO1)_2") (pintype "bidirectional"))
      (node (ref "SPI_PROG") (pin "2") (pinfunction "2_2") (pintype "passive"))
    )
    (net (code "103") (name "QSPI2_SD2") (class "Default")
      (node (ref "IC3") (pin "54") (pinfunction "QSPI_SD2_54") (pintype "bidirectional"))
      (node (ref "IC5") (pin "3") (pinfunction "~{WP}(IO2)_3") (pintype "bidirectional"))
    )
    (net (code "104") (name "QSPI2_SD3") (class "Default")
      (node (ref "IC3") (pin "51") (pinfunction "QSPI_SD3_51") (pintype "bidirectional"))
      (node (ref "IC5") (pin "7") (pinfunction "~{HOLD}(IO3)_7") (pintype "bidirectional"))
    )
    (net (code "105") (name "QSPI_CLK") (class "Default")
      (node (ref "IC2") (pin "52") (pinfunction "QSPI_SCLK_52") (pintype "bidirectional"))
      (node (ref "IC4") (pin "6") (pinfunction "CLK_6") (pintype "bidirectional"))
    )
    (net (code "106") (name "QSPI_SD0") (class "Default")
      (node (ref "IC2") (pin "53") (pinfunction "QSPI_SD0_53") (pintype "bidirectional"))
      (node (ref "IC4") (pin "5") (pinfunction "DI(IO0)_5") (pintype "bidirectional"))
    )
    (net (code "107") (name "QSPI_SD1") (class "Default")
      (node (ref "IC2") (pin "55") (pinfunction "QSPI_SD1_55") (pintype "bidirectional"))
      (node (ref "IC4") (pin "2") (pinfunction "DO(IO1)_2") (pintype "bidirectional"))
    )
    (net (code "108") (name "QSPI_SD2") (class "Default")
      (node (ref "IC2") (pin "54") (pinfunction "QSPI_SD2_54") (pintype "bidirectional"))
      (node (ref "IC4") (pin "3") (pinfunction "~{WP}(IO2)_3") (pintype "bidirectional"))
    )
    (net (code "109") (name "QSPI_SD3") (class "Default")
      (node (ref "IC2") (pin "51") (pinfunction "QSPI_SD3_51") (pintype "bidirectional"))
      (node (ref "IC4") (pin "7") (pinfunction "~{HOLD}(IO3)_7") (pintype "bidirectional"))
    )
    (net (code "110") (name "RP1USB_N") (class "Default")
      (node (ref "R2") (pin "2") (pinfunction "2_2") (pintype "passive"))
      (node (ref "U$1") (pin "10") (pinfunction "D1-_10") (pintype "bidirectional"))
    )
    (net (code "111") (name "RP1USB_P") (class "Default")
      (node (ref "R1") (pin "2") (pinfunction "2_2") (pintype "passive"))
      (node (ref "U$1") (pin "11") (pinfunction "D1+_11") (pintype "bidirectional"))
    )
    (net (code "112") (name "RP2USB_N") (class "Default")
      (node (ref "R17") (pin "2") (pinfunction "2_2") (pintype "passive"))
      (node (ref "U$1") (pin "4") (pinfunction "D4-_4") (pintype "bidirectional"))
    )
    (net (code "113") (name "RP2USB_P") (class "Default")
      (node (ref "R16") (pin "2") (pinfunction "2_2") (pintype "passive"))
      (node (ref "U$1") (pin "5") (pinfunction "D4+_5") (pintype "bidirectional"))
    )
    (net (code "114") (name "RP_SCL") (class "Default")
      (node (ref "I2C_SEL") (pin "2") (pinfunction "2_2") (pintype "passive"))
      (node (ref "IC1") (pin "4") (pinfunction "SCL_4") (pintype "bidirectional"))
      (node (ref "U$1") (pin "27") (pinfunction "SCL_27") (pintype "bidirectional"))
    )
    (net (code "115") (name "RP_SDA") (class "Default")
      (node (ref "I2C_SEL") (pin "4") (pinfunction "4_4") (pintype "passive"))
      (node (ref "IC1") (pin "3") (pinfunction "SDA_3") (pintype "bidirectional"))
      (node (ref "R11") (pin "2") (pinfunction "2_2") (pintype "passive"))
      (node (ref "U$1") (pin "26") (pinfunction "~{OVCR}/SDA_26") (pintype "bidirectional"))
    )
    (net (code "116") (name "SWCLK") (class "Default")
      (node (ref "GPIO_1") (pin "19") (pinfunction "19_19") (pintype "passive"))
      (node (ref "IC2") (pin "24") (pinfunction "SWCLK_24") (pintype "bidirectional"))
    )
    (net (code "117") (name "SWDCLK2") (class "Default")
      (node (ref "GPIO_2") (pin "19") (pinfunction "19_19") (pintype "passive"))
      (node (ref "IC3") (pin "24") (pinfunction "SWCLK_24") (pintype "bidirectional"))
    )
    (net (code "118") (name "SWDIO") (class "Default")
      (node (ref "GPIO_1") (pin "20") (pinfunction "20_20") (pintype "passive"))
      (node (ref "IC2") (pin "25") (pinfunction "SWDIO_25") (pintype "bidirectional"))
    )
    (net (code "119") (name "SWDIO2") (class "Default")
      (node (ref "GPIO_2") (pin "20") (pinfunction "20_20") (pintype "passive"))
      (node (ref "IC3") (pin "25") (pinfunction "SWDIO_25") (pintype "bidirectional"))
    )
    (net (code "120") (name "USBD2_N") (class "Default")
      (node (ref "IC3") (pin "46") (pinfunction "USB_DM_46") (pintype "bidirectional"))
      (node (ref "R17") (pin "1") (pinfunction "1_1") (pintype "passive"))
    )
    (net (code "121") (name "USBD2_P") (class "Default")
      (node (ref "IC3") (pin "47") (pinfunction "USB_DP_47") (pintype "bidirectional"))
      (node (ref "R16") (pin "1") (pinfunction "1_1") (pintype "passive"))
    )
    (net (code "122") (name "USBD_N") (class "Default")
      (node (ref "IC2") (pin "46") (pinfunction "USB_DM_46") (pintype "bidirectional"))
      (node (ref "R2") (pin "1") (pinfunction "1_1") (pintype "passive"))
    )
    (net (code "123") (name "USBD_P") (class "Default")
      (node (ref "IC2") (pin "47") (pinfunction "USB_DP_47") (pintype "bidirectional"))
      (node (ref "R1") (pin "1") (pinfunction "1_1") (pintype "passive"))
    )
    (net (code "124") (name "USB_D2_N") (class "Default")
      (node (ref "U$1") (pin "8") (pinfunction "D2-_8") (pintype "bidirectional"))
      (node (ref "USB_IN2") (pin "2") (pinfunction "D-_2") (pintype "bidirectional"))
    )
    (net (code "125") (name "USB_D2_P") (class "Default")
      (node (ref "U$1") (pin "9") (pinfunction "D2+_9") (pintype "bidirectional"))
      (node (ref "USB_IN2") (pin "3") (pinfunction "D+_3") (pintype "bidirectional"))
    )
    (net (code "126") (name "USB_D3_N") (class "Default")
      (node (ref "U$1") (pin "6") (pinfunction "D3-_6") (pintype "bidirectional"))
      (node (ref "USB_IN1") (pin "2") (pinfunction "D-_2") (pintype "bidirectional"))
    )
    (net (code "127") (name "USB_D3_P") (class "Default")
      (node (ref "U$1") (pin "7") (pinfunction "D3+_7") (pintype "bidirectional"))
      (node (ref "USB_IN1") (pin "3") (pinfunction "D+_3") (pintype "bidirectional"))
    )
    (net (code "128") (name "USB_N") (class "Default")
      (node (ref "U$1") (pin "15") (pinfunction "UD-_15") (pintype "bidirectional"))
      (node (ref "USB_IN") (pin "2") (pinfunction "D-_2") (pintype "bidirectional"))
    )
    (net (code "129") (name "USB_P") (class "Default")
      (node (ref "U$1") (pin "16") (pinfunction "UD+_16") (pintype "bidirectional"))
      (node (ref "USB_IN") (pin "3") (pinfunction "D+_3") (pintype "bidirectional"))
    )
    (net (code "130") (name "VBUS") (class "Default")
      (node (ref "POWER") (pin "1") (pinfunction "1_1") (pintype "bidirectional"))
      (node (ref "POWER") (pin "6") (pinfunction "6_6") (pintype "bidirectional"))
      (node (ref "TP_VBUS") (pin "1") (pinfunction "1_1") (pintype "bidirectional"))
      (node (ref "USB_IN") (pin "1") (pinfunction "VBUS_1") (pintype "bidirectional"))
    )
    (net (code "131") (name "unconnected-(IC6-NC-Pad8)") (class "Default")
      (node (ref "IC6") (pin "8") (pinfunction "NC_8") (pintype "no_connect"))
    )
    (net (code "132") (name "unconnected-(U$1-NC-Pad14)") (class "Default")
      (node (ref "U$1") (pin "14") (pinfunction "NC_14") (pintype "bidirectional"))
    )
    (net (code "133") (name "unconnected-(U$1-NC-Pad18)") (class "Default")
      (node (ref "U$1") (pin "18") (pinfunction "NC_18") (pintype "bidirectional"))
    )
    (net (code "134") (name "unconnected-(U$1-~{PWR}-Pad25)") (class "Default")
      (node (ref "U$1") (pin "25") (pinfunction "~{PWR}_25") (pintype "bidirectional"))
    )
    (net (code "135") (name "unconnected-(USB_IN-ID-Pad4)") (class "Default")
      (node (ref "USB_IN") (pin "4") (pinfunction "ID_4") (pintype "bidirectional"))
    )
    (net (code "136") (name "unconnected-(USB_IN1-ID-Pad4)") (class "Default")
      (node (ref "USB_IN1") (pin "4") (pinfunction "ID_4") (pintype "bidirectional"))
    )
    (net (code "137") (name "unconnected-(USB_IN2-ID-Pad4)") (class "Default")
      (node (ref "USB_IN2") (pin "4") (pinfunction "ID_4") (pintype "bidirectional"))
    )
    (net (code "138") (name "~{QSPI2_SS}") (class "Default")
      (node (ref "IC3") (pin "56") (pinfunction "QSPI_SS_N_56") (pintype "bidirectional"))
      (node (ref "IC5") (pin "1") (pinfunction "/CS_1") (pintype "bidirectional"))
      (node (ref "R18") (pin "2") (pinfunction "2_2") (pintype "passive"))
      (node (ref "SPI_PROG") (pin "4") (pinfunction "4_4") (pintype "passive"))
    )
    (net (code "139") (name "~{QSPI_SS}") (class "Default")
      (node (ref "IC2") (pin "56") (pinfunction "QSPI_SS_N_56") (pintype "bidirectional"))
      (node (ref "IC4") (pin "1") (pinfunction "/CS_1") (pintype "bidirectional"))
      (node (ref "R3") (pin "2") (pinfunction "2_2") (pintype "passive"))
    )
    (net (code "140") (name "~{RESET_RP1}") (class "Default")
      (node (ref "C17") (pin "1") (pinfunction "1_1") (pintype "passive"))
      (node (ref "GPIO_1") (pin "22") (pinfunction "22_22") (pintype "passive"))
      (node (ref "IC2") (pin "26") (pinfunction "RUN_26") (pintype "bidirectional"))
      (node (ref "R10") (pin "1") (pinfunction "1_1") (pintype "passive"))
      (node (ref "RESET_1") (pin "3") (pinfunction "3_3") (pintype "passive"))
      (node (ref "RESET_1") (pin "4") (pinfunction "4_4") (pintype "passive"))
    )
    (net (code "141") (name "~{RESET_RP2}") (class "Default")
      (node (ref "C42") (pin "1") (pinfunction "1_1") (pintype "passive"))
      (node (ref "GPIO_2") (pin "22") (pinfunction "22_22") (pintype "passive"))
      (node (ref "IC3") (pin "26") (pinfunction "RUN_26") (pintype "bidirectional"))
      (node (ref "R24") (pin "1") (pinfunction "1_1") (pintype "passive"))
      (node (ref "RESET_2") (pin "3") (pinfunction "3_3") (pintype "passive"))
      (node (ref "RESET_2") (pin "4") (pinfunction "4_4") (pintype "passive"))
    )
    (net (code "142") (name "~{RESET_USB}") (class "Default")
      (node (ref "C3") (pin "1") (pinfunction "1_1") (pintype "passive"))
      (node (ref "R5") (pin "1") (pinfunction "1_1") (pintype "passive"))
      (node (ref "U$1") (pin "17") (pinfunction "~{RESET}_17") (pintype "bidirectional"))
      (node (ref "USB_RESET") (pin "3") (pinfunction "3_3") (pintype "passive"))
      (node (ref "USB_RESET") (pin "4") (pinfunction "4_4") (pintype "passive"))
    )
  )
)
